# beatrix_B_v1_1.net
KiCad netlist of a schematic drawn in EAGLE
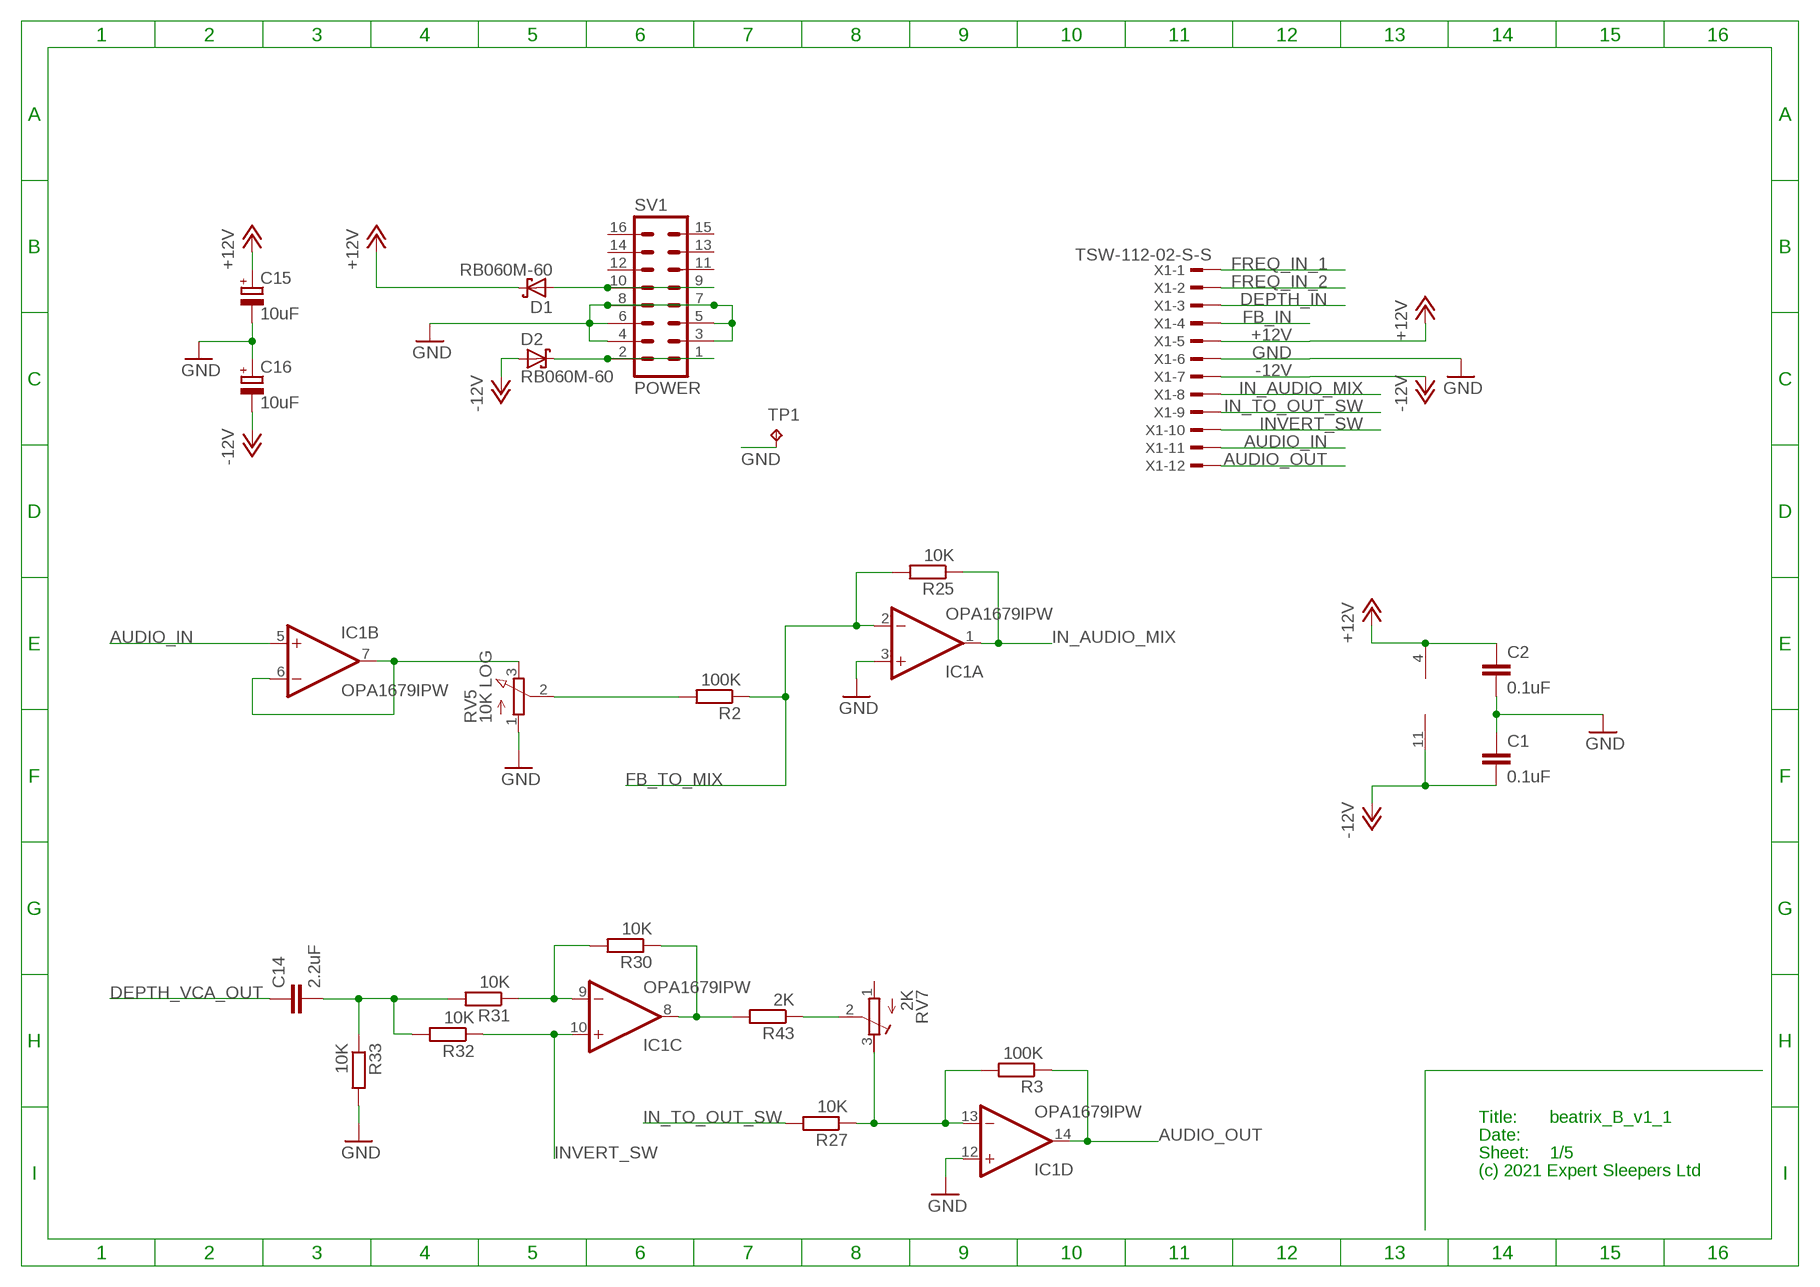
[diagram p0: schematic, sheet 1]
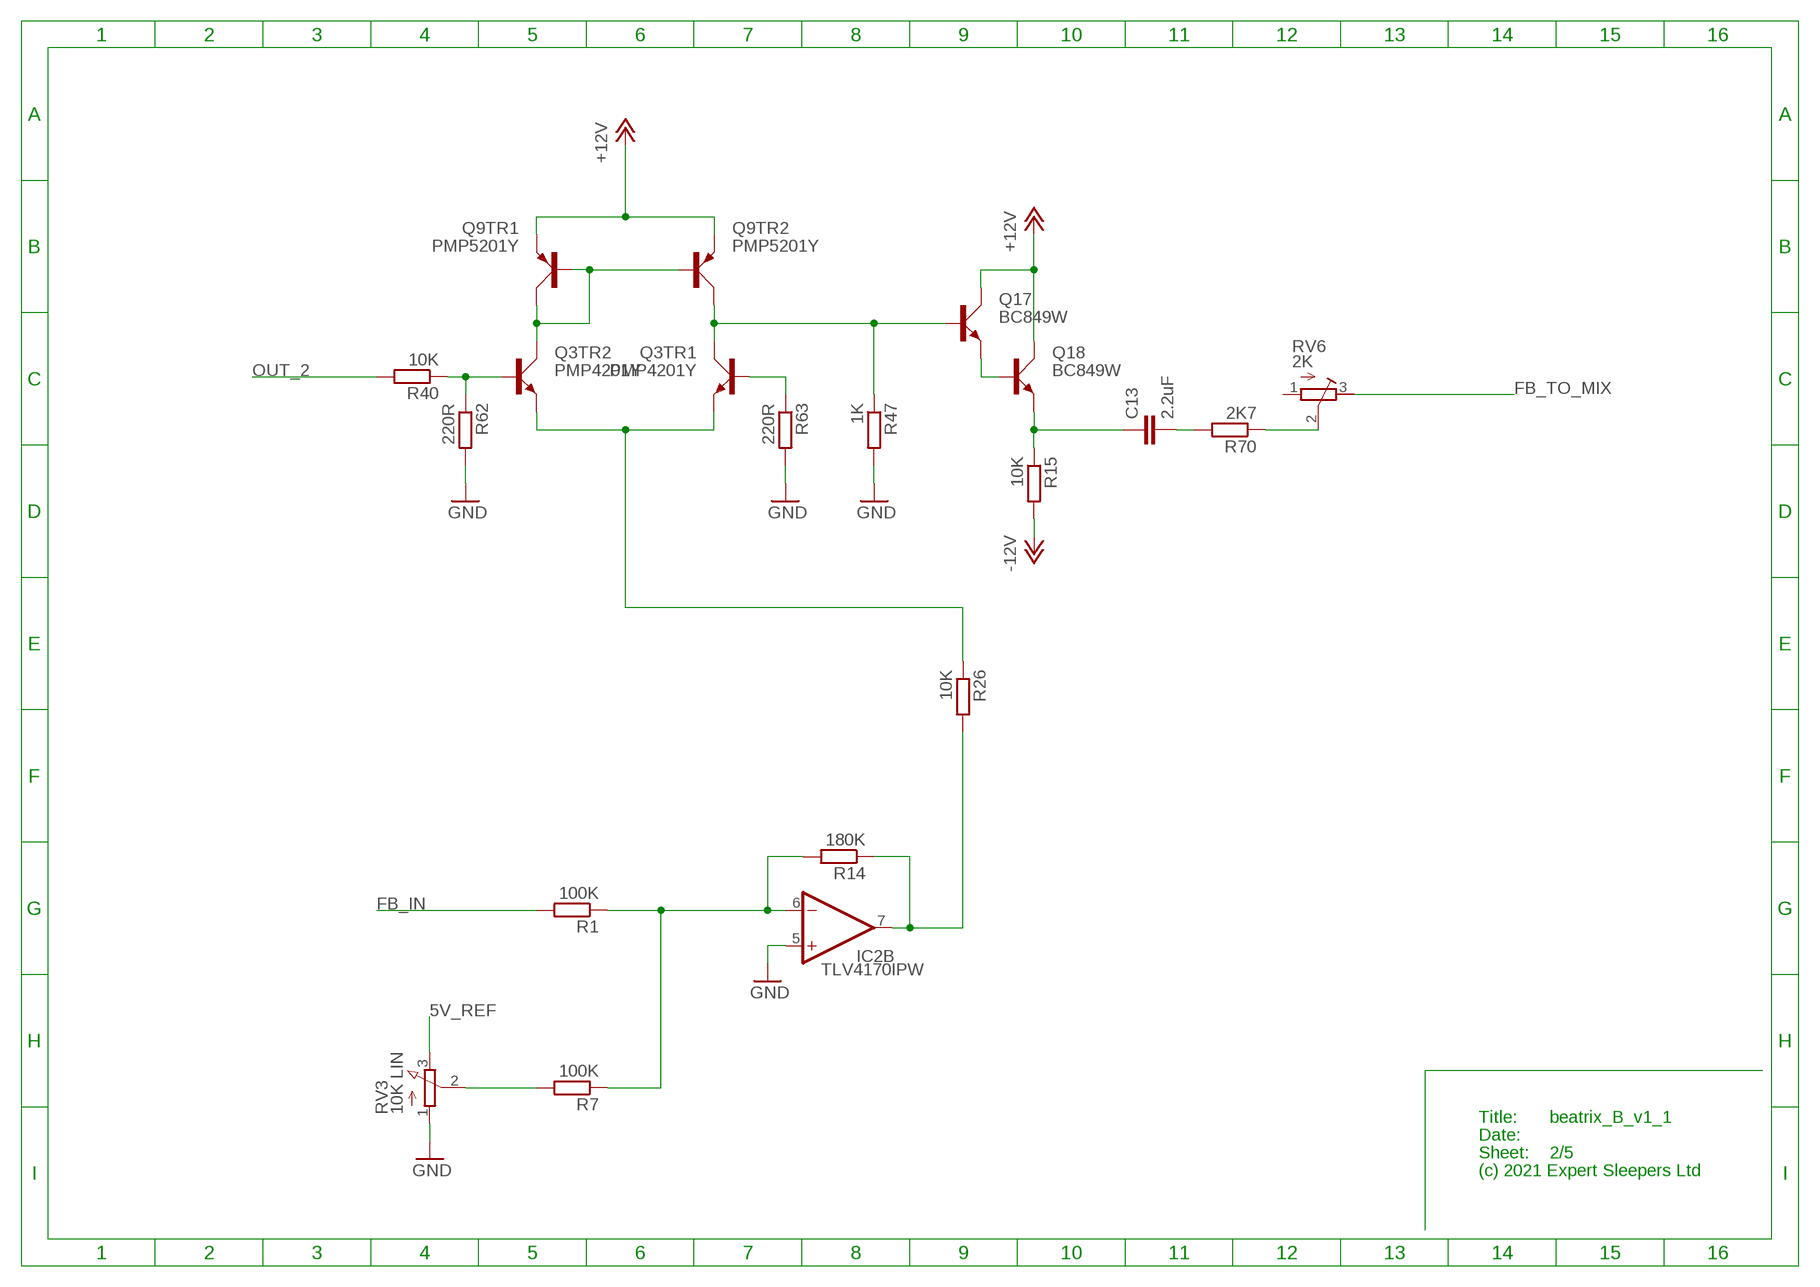
[diagram p1: schematic, sheet 2]
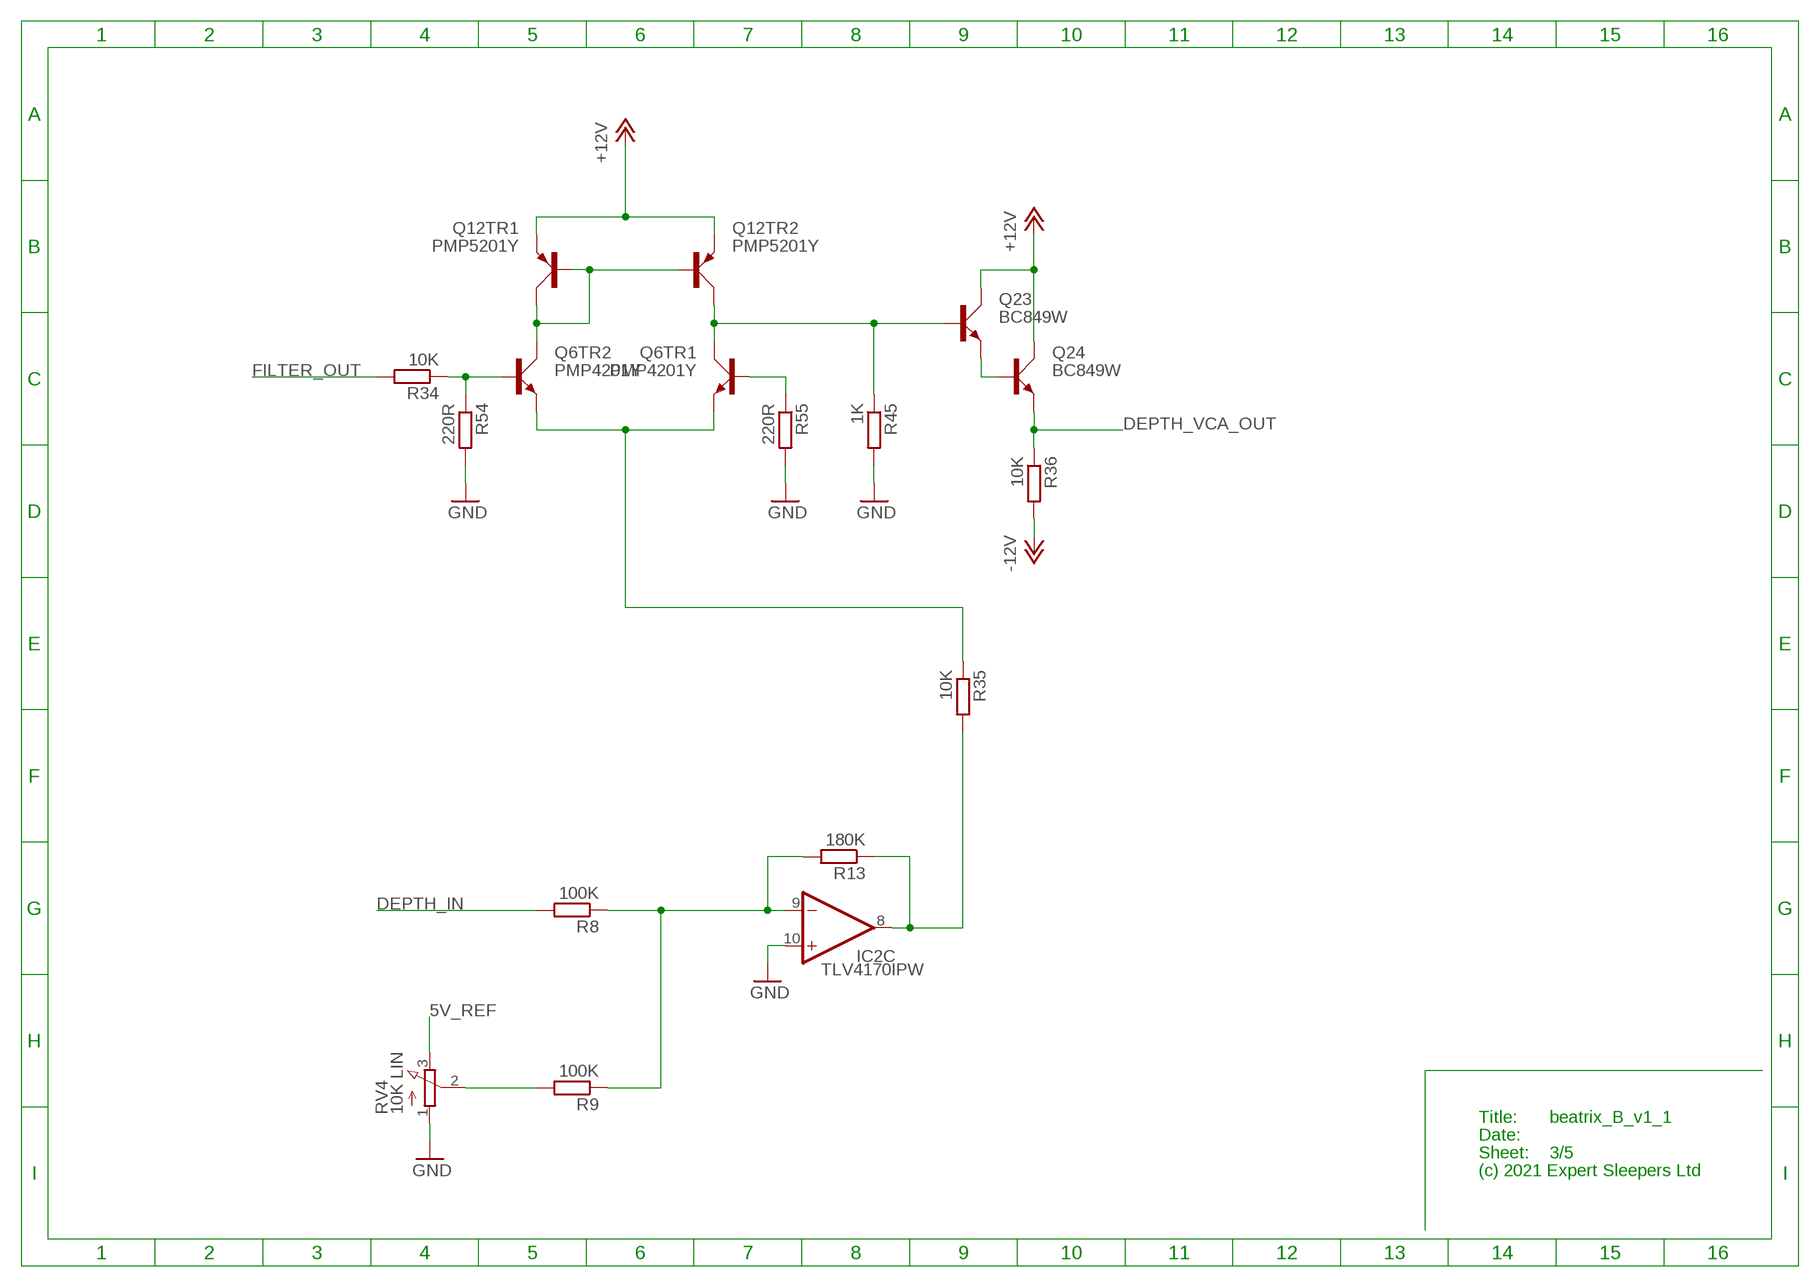
[diagram p2: schematic, sheet 3]
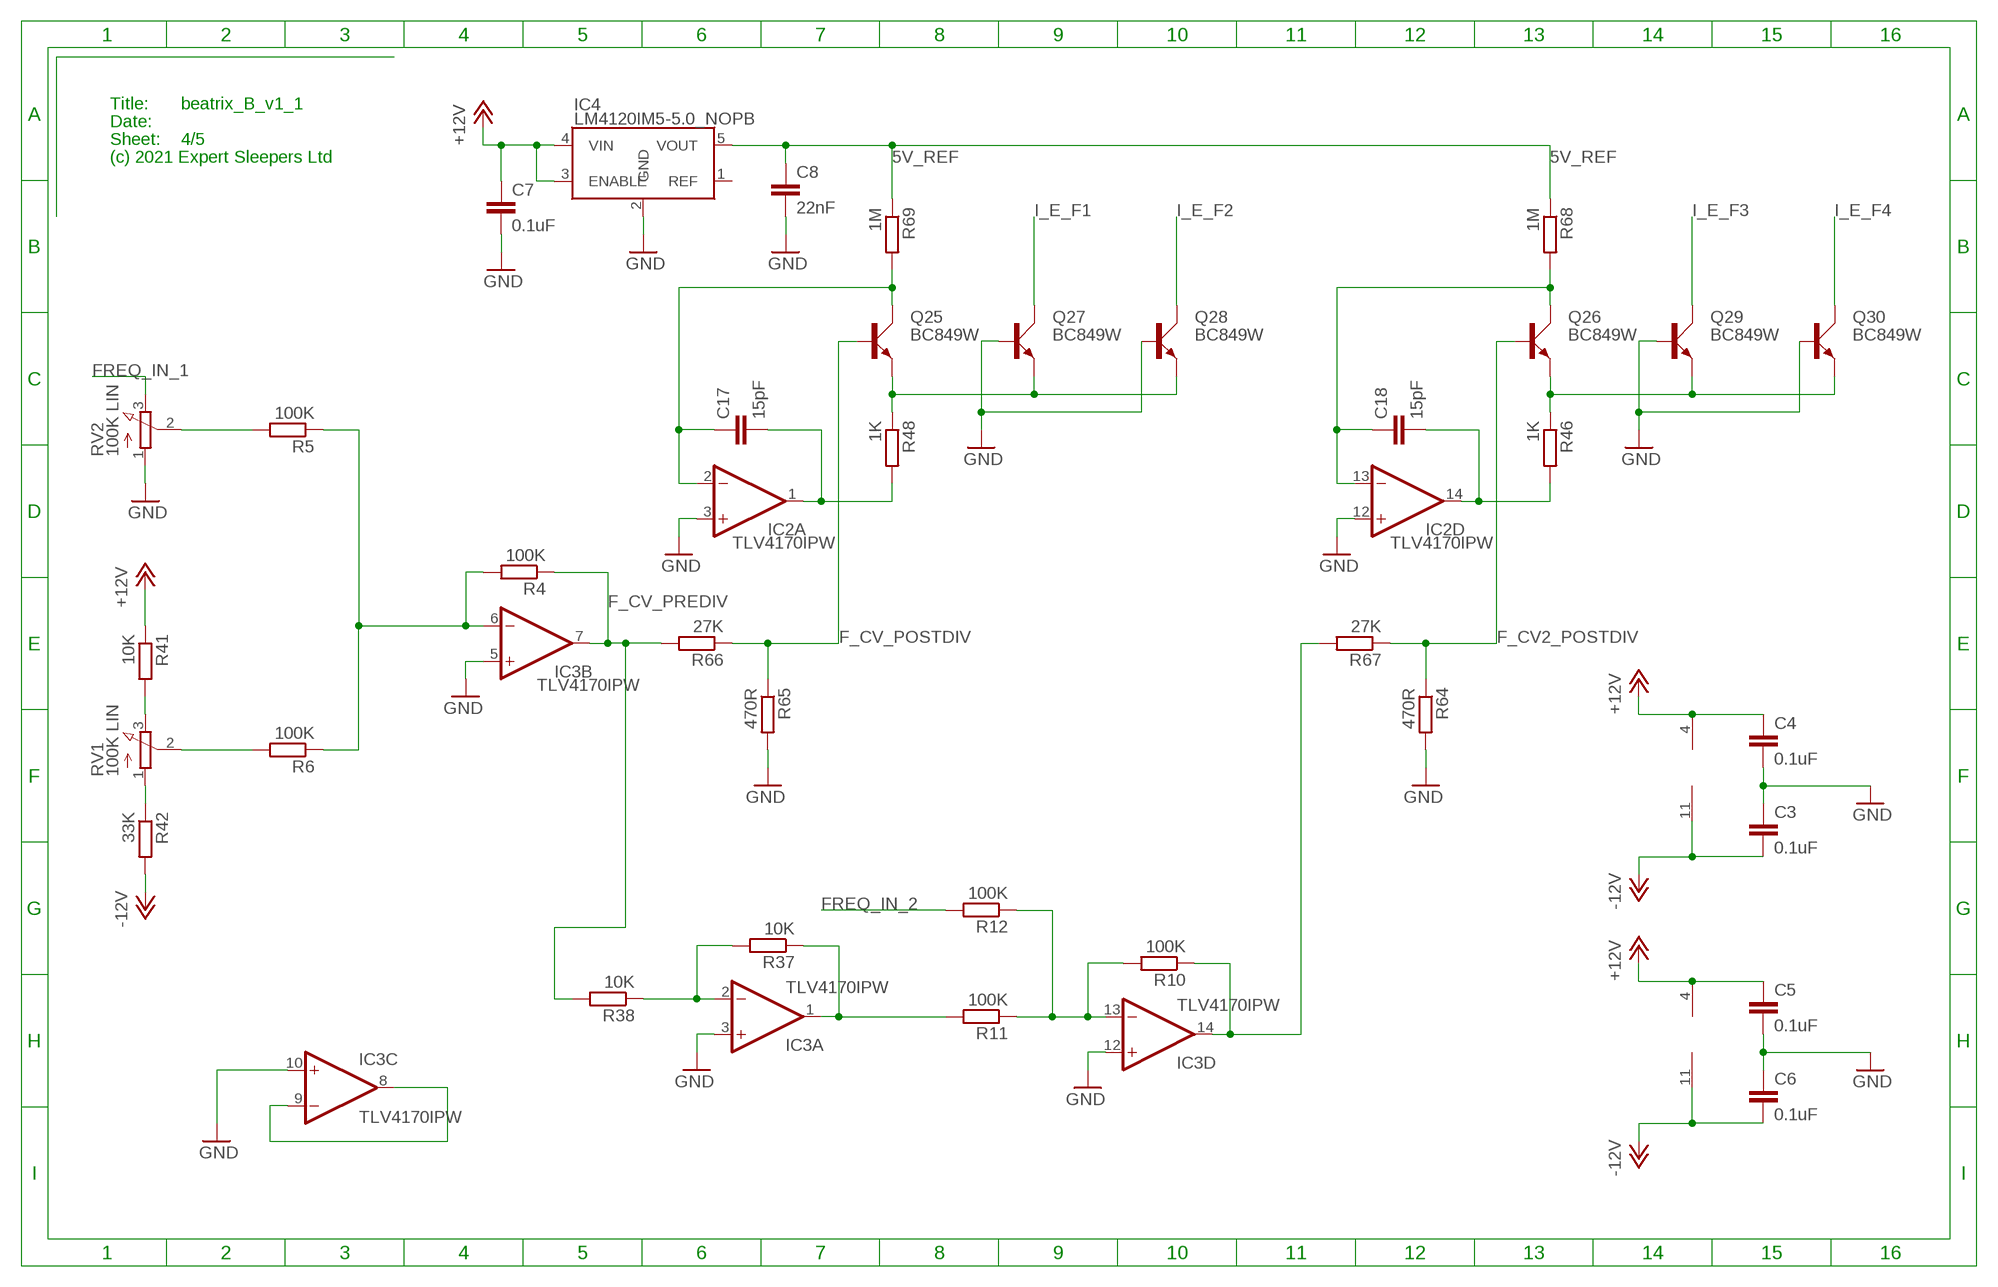
[diagram p3: schematic, sheet 4]
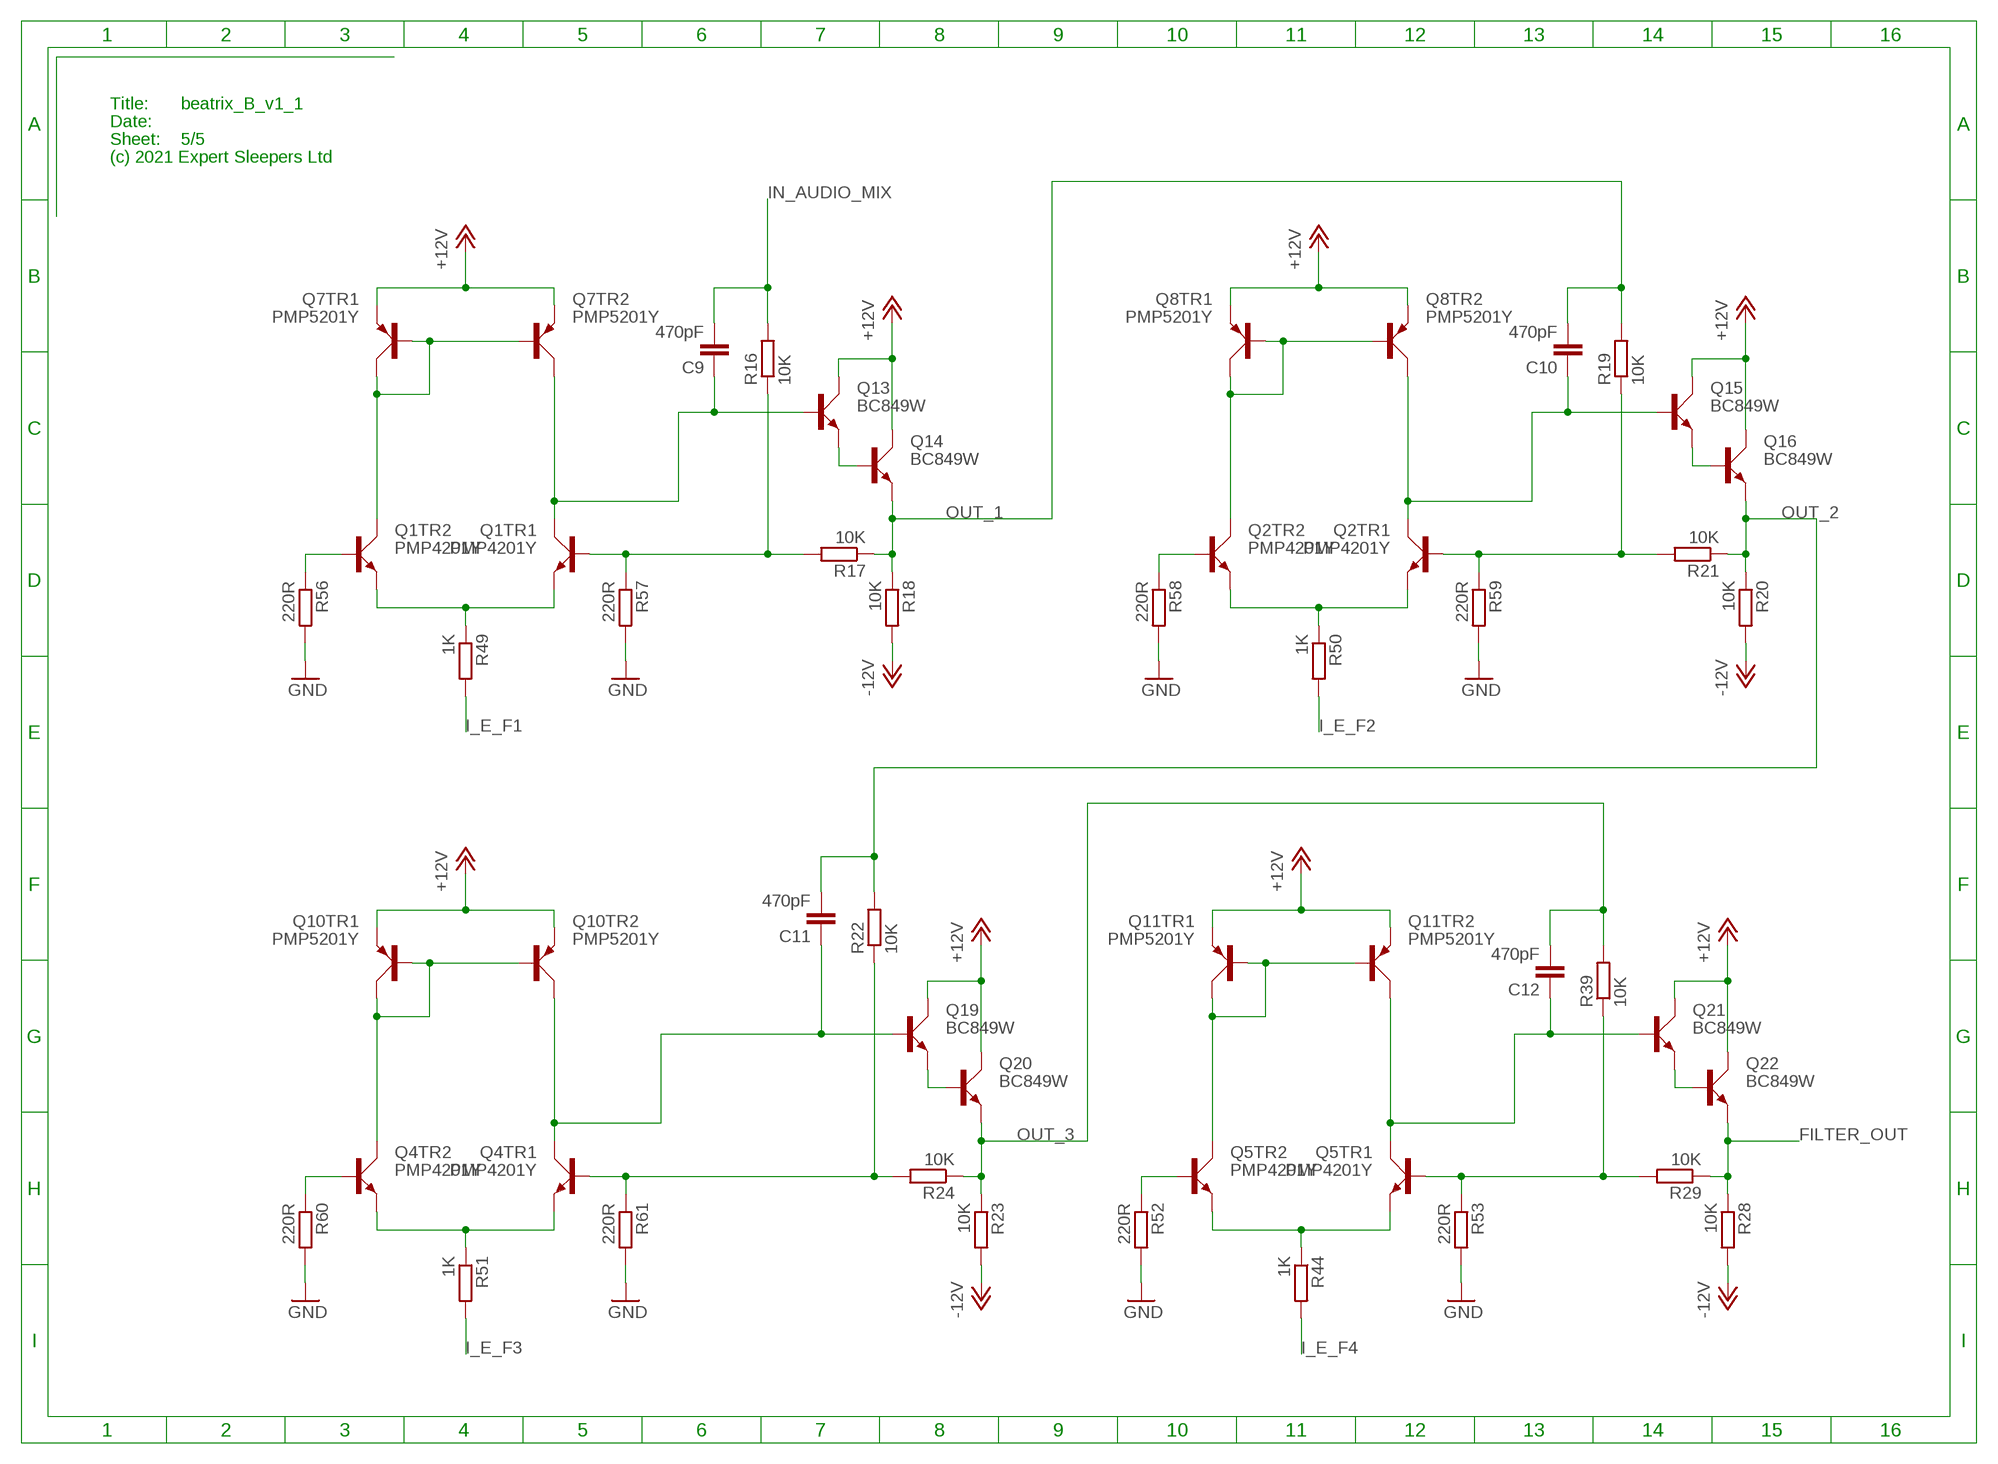
[diagram p4: schematic, sheet 5]

(export (version "E")
  (design (tool "Eeschema 10.0.6"))
  (components
    (comp (ref "C3")
      (value "0.1uF")
      (footprint "eagle-import:C0402")
      (libsource (lib "eagle-import") (part "C-EUC0402"))
    )
    (comp (ref "C4")
      (value "0.1uF")
      (footprint "eagle-import:C0402")
      (libsource (lib "eagle-import") (part "C-EUC0402"))
    )
    (comp (ref "C5")
      (value "0.1uF")
      (footprint "eagle-import:C0402")
      (libsource (lib "eagle-import") (part "C-EUC0402"))
    )
    (comp (ref "C6")
      (value "0.1uF")
      (footprint "eagle-import:C0402")
      (libsource (lib "eagle-import") (part "C-EUC0402"))
    )
    (comp (ref "C7")
      (value "0.1uF")
      (footprint "eagle-import:C0402")
      (libsource (lib "eagle-import") (part "C-EUC0402"))
    )
    (comp (ref "C8")
      (value "22nF")
      (footprint "eagle-import:C0402")
      (libsource (lib "eagle-import") (part "C-EUC0402"))
    )
    (comp (ref "C17")
      (value "15pF")
      (footprint "eagle-import:C0402")
      (libsource (lib "eagle-import") (part "C-EUC0402"))
    )
    (comp (ref "C18")
      (value "15pF")
      (footprint "eagle-import:C0402")
      (libsource (lib "eagle-import") (part "C-EUC0402"))
    )
    (comp (ref "IC2")
      (value "TLV4170IPW")
      (footprint "eagle-import:PW_R-PDSO-G14")
      (libsource (lib "eagle-import") (part "TL074PW"))
    )
    (comp (ref "IC3")
      (value "TLV4170IPW")
      (footprint "eagle-import:PW_R-PDSO-G14")
      (libsource (lib "eagle-import") (part "TL074PW"))
    )
    (comp (ref "IC4")
      (value "LM4120IM5-5.0_NOPB")
      (footprint "eagle-import:SOT95P280X145-5N")
      (fields
        (field (name "ARROW_PART_NUMBER") "LM4120IM5-5.0/NOPB")
        (field (name "MOUSER_PART_NUMBER") "926-LM4120IM550NOPB")
      )
      (libsource (lib "eagle-import") (part "LM4120IM5-5.0_NOPB"))
    )
    (comp (ref "Q25")
      (value "BC849W")
      (footprint "eagle-import:SOT323")
      (libsource (lib "eagle-import") (part "BC849W"))
    )
    (comp (ref "Q26")
      (value "BC849W")
      (footprint "eagle-import:SOT323")
      (libsource (lib "eagle-import") (part "BC849W"))
    )
    (comp (ref "Q27")
      (value "BC849W")
      (footprint "eagle-import:SOT323")
      (libsource (lib "eagle-import") (part "BC849W"))
    )
    (comp (ref "Q28")
      (value "BC849W")
      (footprint "eagle-import:SOT323")
      (libsource (lib "eagle-import") (part "BC849W"))
    )
    (comp (ref "Q29")
      (value "BC849W")
      (footprint "eagle-import:SOT323")
      (libsource (lib "eagle-import") (part "BC849W"))
    )
    (comp (ref "Q30")
      (value "BC849W")
      (footprint "eagle-import:SOT323")
      (libsource (lib "eagle-import") (part "BC849W"))
    )
    (comp (ref "R4")
      (value "100K")
      (footprint "eagle-import:R0603")
      (libsource (lib "eagle-import") (part "R-EU_R0603"))
    )
    (comp (ref "R5")
      (value "100K")
      (footprint "eagle-import:R0603")
      (libsource (lib "eagle-import") (part "R-EU_R0603"))
    )
    (comp (ref "R6")
      (value "100K")
      (footprint "eagle-import:R0603")
      (libsource (lib "eagle-import") (part "R-EU_R0603"))
    )
    (comp (ref "R10")
      (value "100K")
      (footprint "eagle-import:R0603")
      (libsource (lib "eagle-import") (part "R-EU_R0603"))
    )
    (comp (ref "R11")
      (value "100K")
      (footprint "eagle-import:R0603")
      (libsource (lib "eagle-import") (part "R-EU_R0603"))
    )
    (comp (ref "R12")
      (value "100K")
      (footprint "eagle-import:R0603")
      (libsource (lib "eagle-import") (part "R-EU_R0603"))
    )
    (comp (ref "R37")
      (value "10K")
      (footprint "eagle-import:R0603")
      (libsource (lib "eagle-import") (part "R-EU_R0603"))
    )
    (comp (ref "R38")
      (value "10K")
      (footprint "eagle-import:R0603")
      (libsource (lib "eagle-import") (part "R-EU_R0603"))
    )
    (comp (ref "R41")
      (value "10K")
      (footprint "eagle-import:R0603")
      (libsource (lib "eagle-import") (part "R-EU_R0603"))
    )
    (comp (ref "R42")
      (value "33K")
      (footprint "eagle-import:R0603")
      (libsource (lib "eagle-import") (part "R-EU_R0603"))
    )
    (comp (ref "R46")
      (value "1K")
      (footprint "eagle-import:R0603")
      (libsource (lib "eagle-import") (part "R-EU_R0603"))
    )
    (comp (ref "R48")
      (value "1K")
      (footprint "eagle-import:R0603")
      (libsource (lib "eagle-import") (part "R-EU_R0603"))
    )
    (comp (ref "R64")
      (value "470R")
      (footprint "eagle-import:R0603")
      (libsource (lib "eagle-import") (part "R-EU_R0603"))
    )
    (comp (ref "R65")
      (value "470R")
      (footprint "eagle-import:R0603")
      (libsource (lib "eagle-import") (part "R-EU_R0603"))
    )
    (comp (ref "R66")
      (value "27K")
      (footprint "eagle-import:R0603")
      (libsource (lib "eagle-import") (part "R-EU_R0603"))
    )
    (comp (ref "R67")
      (value "27K")
      (footprint "eagle-import:R0603")
      (libsource (lib "eagle-import") (part "R-EU_R0603"))
    )
    (comp (ref "R68")
      (value "1M")
      (footprint "eagle-import:R0603")
      (libsource (lib "eagle-import") (part "R-EU_R0603"))
    )
    (comp (ref "R69")
      (value "1M")
      (footprint "eagle-import:R0603")
      (libsource (lib "eagle-import") (part "R-EU_R0603"))
    )
    (comp (ref "RV1")
      (value "100K LIN")
      (footprint "eagle-import:RD1610NOA0X")
      (libsource (lib "eagle-import") (part "RD1610NOA0X"))
    )
    (comp (ref "RV2")
      (value "100K LIN")
      (footprint "eagle-import:RD1610NOA0X")
      (libsource (lib "eagle-import") (part "RD1610NOA0X"))
    )
    (comp (ref "Q6")
      (value "PMP4201Y")
      (footprint "eagle-import:SOT65P210X110-6N")
      (fields
        (field (name "ARROW_PART_NUMBER") "PMP4201Y,135")
        (field (name "MOUSER_PART_NUMBER") "771-PMP4201Y135")
      )
      (libsource (lib "eagle-import") (part "PMP4201Y"))
    )
    (comp (ref "Q12")
      (value "PMP5201Y")
      (footprint "eagle-import:SOT65P210X110-6N")
      (fields
        (field (name "ARROW_PART_NUMBER") "PMP5201Y,135")
        (field (name "MOUSER_PART_NUMBER") "771-PMP5201Y135")
      )
      (libsource (lib "eagle-import") (part "PMP5201Y"))
    )
    (comp (ref "Q23")
      (value "BC849W")
      (footprint "eagle-import:SOT323")
      (libsource (lib "eagle-import") (part "BC849W"))
    )
    (comp (ref "Q24")
      (value "BC849W")
      (footprint "eagle-import:SOT323")
      (libsource (lib "eagle-import") (part "BC849W"))
    )
    (comp (ref "R8")
      (value "100K")
      (footprint "eagle-import:R0603")
      (libsource (lib "eagle-import") (part "R-EU_R0603"))
    )
    (comp (ref "R9")
      (value "100K")
      (footprint "eagle-import:R0603")
      (libsource (lib "eagle-import") (part "R-EU_R0603"))
    )
    (comp (ref "R13")
      (value "180K")
      (footprint "eagle-import:R0603")
      (libsource (lib "eagle-import") (part "R-EU_R0603"))
    )
    (comp (ref "R34")
      (value "10K")
      (footprint "eagle-import:R0603")
      (libsource (lib "eagle-import") (part "R-EU_R0603"))
    )
    (comp (ref "R35")
      (value "10K")
      (footprint "eagle-import:R0603")
      (libsource (lib "eagle-import") (part "R-EU_R0603"))
    )
    (comp (ref "R36")
      (value "10K")
      (footprint "eagle-import:R0603")
      (libsource (lib "eagle-import") (part "R-EU_R0603"))
    )
    (comp (ref "R45")
      (value "1K")
      (footprint "eagle-import:R0603")
      (libsource (lib "eagle-import") (part "R-EU_R0603"))
    )
    (comp (ref "R54")
      (value "220R")
      (footprint "eagle-import:R0603")
      (libsource (lib "eagle-import") (part "R-EU_R0603"))
    )
    (comp (ref "R55")
      (value "220R")
      (footprint "eagle-import:R0603")
      (libsource (lib "eagle-import") (part "R-EU_R0603"))
    )
    (comp (ref "RV4")
      (value "10K LIN")
      (footprint "eagle-import:RD1610NOA0X")
      (libsource (lib "eagle-import") (part "RD1610NOA0X"))
    )
    (comp (ref "C13")
      (value "2.2uF")
      (footprint "eagle-import:C0805")
      (libsource (lib "eagle-import") (part "C-EUC0805"))
    )
    (comp (ref "Q3")
      (value "PMP4201Y")
      (footprint "eagle-import:SOT65P210X110-6N")
      (fields
        (field (name "ARROW_PART_NUMBER") "PMP4201Y,135")
        (field (name "MOUSER_PART_NUMBER") "771-PMP4201Y135")
      )
      (libsource (lib "eagle-import") (part "PMP4201Y"))
    )
    (comp (ref "Q9")
      (value "PMP5201Y")
      (footprint "eagle-import:SOT65P210X110-6N")
      (fields
        (field (name "ARROW_PART_NUMBER") "PMP5201Y,135")
        (field (name "MOUSER_PART_NUMBER") "771-PMP5201Y135")
      )
      (libsource (lib "eagle-import") (part "PMP5201Y"))
    )
    (comp (ref "Q17")
      (value "BC849W")
      (footprint "eagle-import:SOT323")
      (libsource (lib "eagle-import") (part "BC849W"))
    )
    (comp (ref "Q18")
      (value "BC849W")
      (footprint "eagle-import:SOT323")
      (libsource (lib "eagle-import") (part "BC849W"))
    )
    (comp (ref "R1")
      (value "100K")
      (footprint "eagle-import:R0603")
      (libsource (lib "eagle-import") (part "R-EU_R0603"))
    )
    (comp (ref "R7")
      (value "100K")
      (footprint "eagle-import:R0603")
      (libsource (lib "eagle-import") (part "R-EU_R0603"))
    )
    (comp (ref "R14")
      (value "180K")
      (footprint "eagle-import:R0603")
      (libsource (lib "eagle-import") (part "R-EU_R0603"))
    )
    (comp (ref "R15")
      (value "10K")
      (footprint "eagle-import:R0603")
      (libsource (lib "eagle-import") (part "R-EU_R0603"))
    )
    (comp (ref "R26")
      (value "10K")
      (footprint "eagle-import:R0603")
      (libsource (lib "eagle-import") (part "R-EU_R0603"))
    )
    (comp (ref "R40")
      (value "10K")
      (footprint "eagle-import:R0603")
      (libsource (lib "eagle-import") (part "R-EU_R0603"))
    )
    (comp (ref "R47")
      (value "1K")
      (footprint "eagle-import:R0603")
      (libsource (lib "eagle-import") (part "R-EU_R0603"))
    )
    (comp (ref "R62")
      (value "220R")
      (footprint "eagle-import:R0603")
      (libsource (lib "eagle-import") (part "R-EU_R0603"))
    )
    (comp (ref "R63")
      (value "220R")
      (footprint "eagle-import:R0603")
      (libsource (lib "eagle-import") (part "R-EU_R0603"))
    )
    (comp (ref "R70")
      (value "2K7")
      (footprint "eagle-import:R0603")
      (libsource (lib "eagle-import") (part "R-EU_R0603"))
    )
    (comp (ref "RV3")
      (value "10K LIN")
      (footprint "eagle-import:RD1610NOA0X")
      (libsource (lib "eagle-import") (part "RD1610NOA0X"))
    )
    (comp (ref "RV6")
      (value "2K")
      (footprint "eagle-import:TC33X")
      (libsource (lib "eagle-import") (part "TC33X"))
    )
    (comp (ref "C9")
      (value "470pF")
      (footprint "eagle-import:C0603")
      (libsource (lib "eagle-import") (part "C-EUC0603"))
    )
    (comp (ref "C10")
      (value "470pF")
      (footprint "eagle-import:C0603")
      (libsource (lib "eagle-import") (part "C-EUC0603"))
    )
    (comp (ref "C11")
      (value "470pF")
      (footprint "eagle-import:C0603")
      (libsource (lib "eagle-import") (part "C-EUC0603"))
    )
    (comp (ref "C12")
      (value "470pF")
      (footprint "eagle-import:C0603")
      (libsource (lib "eagle-import") (part "C-EUC0603"))
    )
    (comp (ref "Q1")
      (value "PMP4201Y")
      (footprint "eagle-import:SOT65P210X110-6N")
      (fields
        (field (name "ARROW_PART_NUMBER") "PMP4201Y,135")
        (field (name "MOUSER_PART_NUMBER") "771-PMP4201Y135")
      )
      (libsource (lib "eagle-import") (part "PMP4201Y"))
    )
    (comp (ref "Q2")
      (value "PMP4201Y")
      (footprint "eagle-import:SOT65P210X110-6N")
      (fields
        (field (name "ARROW_PART_NUMBER") "PMP4201Y,135")
        (field (name "MOUSER_PART_NUMBER") "771-PMP4201Y135")
      )
      (libsource (lib "eagle-import") (part "PMP4201Y"))
    )
    (comp (ref "Q4")
      (value "PMP4201Y")
      (footprint "eagle-import:SOT65P210X110-6N")
      (fields
        (field (name "ARROW_PART_NUMBER") "PMP4201Y,135")
        (field (name "MOUSER_PART_NUMBER") "771-PMP4201Y135")
      )
      (libsource (lib "eagle-import") (part "PMP4201Y"))
    )
    (comp (ref "Q5")
      (value "PMP4201Y")
      (footprint "eagle-import:SOT65P210X110-6N")
      (fields
        (field (name "ARROW_PART_NUMBER") "PMP4201Y,135")
        (field (name "MOUSER_PART_NUMBER") "771-PMP4201Y135")
      )
      (libsource (lib "eagle-import") (part "PMP4201Y"))
    )
    (comp (ref "Q7")
      (value "PMP5201Y")
      (footprint "eagle-import:SOT65P210X110-6N")
      (fields
        (field (name "ARROW_PART_NUMBER") "PMP5201Y,135")
        (field (name "MOUSER_PART_NUMBER") "771-PMP5201Y135")
      )
      (libsource (lib "eagle-import") (part "PMP5201Y"))
    )
    (comp (ref "Q8")
      (value "PMP5201Y")
      (footprint "eagle-import:SOT65P210X110-6N")
      (fields
        (field (name "ARROW_PART_NUMBER") "PMP5201Y,135")
        (field (name "MOUSER_PART_NUMBER") "771-PMP5201Y135")
      )
      (libsource (lib "eagle-import") (part "PMP5201Y"))
    )
    (comp (ref "Q10")
      (value "PMP5201Y")
      (footprint "eagle-import:SOT65P210X110-6N")
      (fields
        (field (name "ARROW_PART_NUMBER") "PMP5201Y,135")
        (field (name "MOUSER_PART_NUMBER") "771-PMP5201Y135")
      )
      (libsource (lib "eagle-import") (part "PMP5201Y"))
    )
    (comp (ref "Q11")
      (value "PMP5201Y")
      (footprint "eagle-import:SOT65P210X110-6N")
      (fields
        (field (name "ARROW_PART_NUMBER") "PMP5201Y,135")
        (field (name "MOUSER_PART_NUMBER") "771-PMP5201Y135")
      )
      (libsource (lib "eagle-import") (part "PMP5201Y"))
    )
    (comp (ref "Q13")
      (value "BC849W")
      (footprint "eagle-import:SOT323")
      (libsource (lib "eagle-import") (part "BC849W"))
    )
    (comp (ref "Q14")
      (value "BC849W")
      (footprint "eagle-import:SOT323")
      (libsource (lib "eagle-import") (part "BC849W"))
    )
    (comp (ref "Q15")
      (value "BC849W")
      (footprint "eagle-import:SOT323")
      (libsource (lib "eagle-import") (part "BC849W"))
    )
    (comp (ref "Q16")
      (value "BC849W")
      (footprint "eagle-import:SOT323")
      (libsource (lib "eagle-import") (part "BC849W"))
    )
    (comp (ref "Q19")
      (value "BC849W")
      (footprint "eagle-import:SOT323")
      (libsource (lib "eagle-import") (part "BC849W"))
    )
    (comp (ref "Q20")
      (value "BC849W")
      (footprint "eagle-import:SOT323")
      (libsource (lib "eagle-import") (part "BC849W"))
    )
    (comp (ref "Q21")
      (value "BC849W")
      (footprint "eagle-import:SOT323")
      (libsource (lib "eagle-import") (part "BC849W"))
    )
    (comp (ref "Q22")
      (value "BC849W")
      (footprint "eagle-import:SOT323")
      (libsource (lib "eagle-import") (part "BC849W"))
    )
    (comp (ref "R16")
      (value "10K")
      (footprint "eagle-import:R0603")
      (libsource (lib "eagle-import") (part "R-EU_R0603"))
    )
    (comp (ref "R17")
      (value "10K")
      (footprint "eagle-import:R0603")
      (libsource (lib "eagle-import") (part "R-EU_R0603"))
    )
    (comp (ref "R18")
      (value "10K")
      (footprint "eagle-import:R0603")
      (libsource (lib "eagle-import") (part "R-EU_R0603"))
    )
    (comp (ref "R19")
      (value "10K")
      (footprint "eagle-import:R0603")
      (libsource (lib "eagle-import") (part "R-EU_R0603"))
    )
    (comp (ref "R20")
      (value "10K")
      (footprint "eagle-import:R0603")
      (libsource (lib "eagle-import") (part "R-EU_R0603"))
    )
    (comp (ref "R21")
      (value "10K")
      (footprint "eagle-import:R0603")
      (libsource (lib "eagle-import") (part "R-EU_R0603"))
    )
    (comp (ref "R22")
      (value "10K")
      (footprint "eagle-import:R0603")
      (libsource (lib "eagle-import") (part "R-EU_R0603"))
    )
    (comp (ref "R23")
      (value "10K")
      (footprint "eagle-import:R0603")
      (libsource (lib "eagle-import") (part "R-EU_R0603"))
    )
    (comp (ref "R24")
      (value "10K")
      (footprint "eagle-import:R0603")
      (libsource (lib "eagle-import") (part "R-EU_R0603"))
    )
    (comp (ref "R28")
      (value "10K")
      (footprint "eagle-import:R0603")
      (libsource (lib "eagle-import") (part "R-EU_R0603"))
    )
    (comp (ref "R29")
      (value "10K")
      (footprint "eagle-import:R0603")
      (libsource (lib "eagle-import") (part "R-EU_R0603"))
    )
    (comp (ref "R39")
      (value "10K")
      (footprint "eagle-import:R0603")
      (libsource (lib "eagle-import") (part "R-EU_R0603"))
    )
    (comp (ref "R44")
      (value "1K")
      (footprint "eagle-import:R0603")
      (libsource (lib "eagle-import") (part "R-EU_R0603"))
    )
    (comp (ref "R49")
      (value "1K")
      (footprint "eagle-import:R0603")
      (libsource (lib "eagle-import") (part "R-EU_R0603"))
    )
    (comp (ref "R50")
      (value "1K")
      (footprint "eagle-import:R0603")
      (libsource (lib "eagle-import") (part "R-EU_R0603"))
    )
    (comp (ref "R51")
      (value "1K")
      (footprint "eagle-import:R0603")
      (libsource (lib "eagle-import") (part "R-EU_R0603"))
    )
    (comp (ref "R52")
      (value "220R")
      (footprint "eagle-import:R0603")
      (libsource (lib "eagle-import") (part "R-EU_R0603"))
    )
    (comp (ref "R53")
      (value "220R")
      (footprint "eagle-import:R0603")
      (libsource (lib "eagle-import") (part "R-EU_R0603"))
    )
    (comp (ref "R56")
      (value "220R")
      (footprint "eagle-import:R0603")
      (libsource (lib "eagle-import") (part "R-EU_R0603"))
    )
    (comp (ref "R57")
      (value "220R")
      (footprint "eagle-import:R0603")
      (libsource (lib "eagle-import") (part "R-EU_R0603"))
    )
    (comp (ref "R58")
      (value "220R")
      (footprint "eagle-import:R0603")
      (libsource (lib "eagle-import") (part "R-EU_R0603"))
    )
    (comp (ref "R59")
      (value "220R")
      (footprint "eagle-import:R0603")
      (libsource (lib "eagle-import") (part "R-EU_R0603"))
    )
    (comp (ref "R60")
      (value "220R")
      (footprint "eagle-import:R0603")
      (libsource (lib "eagle-import") (part "R-EU_R0603"))
    )
    (comp (ref "R61")
      (value "220R")
      (footprint "eagle-import:R0603")
      (libsource (lib "eagle-import") (part "R-EU_R0603"))
    )
    (comp (ref "C1")
      (value "0.1uF")
      (footprint "eagle-import:C0402")
      (libsource (lib "eagle-import") (part "C-EUC0402"))
    )
    (comp (ref "C2")
      (value "0.1uF")
      (footprint "eagle-import:C0402")
      (libsource (lib "eagle-import") (part "C-EUC0402"))
    )
    (comp (ref "C14")
      (value "2.2uF")
      (footprint "eagle-import:C0805")
      (libsource (lib "eagle-import") (part "C-EUC0805"))
    )
    (comp (ref "C15")
      (value "10uF")
      (footprint "eagle-import:UD-4X5,8_NICHICON")
      (libsource (lib "eagle-import") (part "CPOL-EUUD-4X5,8"))
    )
    (comp (ref "C16")
      (value "10uF")
      (footprint "eagle-import:UD-4X5,8_NICHICON")
      (libsource (lib "eagle-import") (part "CPOL-EUUD-4X5,8"))
    )
    (comp (ref "D1")
      (value "RB060M-60")
      (footprint "eagle-import:SOD123FL")
      (libsource (lib "eagle-import") (part "RB060M-60"))
    )
    (comp (ref "D2")
      (value "RB060M-60")
      (footprint "eagle-import:SOD123FL")
      (libsource (lib "eagle-import") (part "RB060M-60"))
    )
    (comp (ref "IC1")
      (value "OPA1679IPW")
      (footprint "eagle-import:PW_R-PDSO-G14")
      (libsource (lib "eagle-import") (part "TL074PW"))
    )
    (comp (ref "R2")
      (value "100K")
      (footprint "eagle-import:R0603")
      (libsource (lib "eagle-import") (part "R-EU_R0603"))
    )
    (comp (ref "R3")
      (value "100K")
      (footprint "eagle-import:R0603")
      (libsource (lib "eagle-import") (part "R-EU_R0603"))
    )
    (comp (ref "R25")
      (value "10K")
      (footprint "eagle-import:R0603")
      (libsource (lib "eagle-import") (part "R-EU_R0603"))
    )
    (comp (ref "R27")
      (value "10K")
      (footprint "eagle-import:R0603")
      (libsource (lib "eagle-import") (part "R-EU_R0603"))
    )
    (comp (ref "R30")
      (value "10K")
      (footprint "eagle-import:R0603")
      (libsource (lib "eagle-import") (part "R-EU_R0603"))
    )
    (comp (ref "R31")
      (value "10K")
      (footprint "eagle-import:R0603")
      (libsource (lib "eagle-import") (part "R-EU_R0603"))
    )
    (comp (ref "R32")
      (value "10K")
      (footprint "eagle-import:R0603")
      (libsource (lib "eagle-import") (part "R-EU_R0603"))
    )
    (comp (ref "R33")
      (value "10K")
      (footprint "eagle-import:R0603")
      (libsource (lib "eagle-import") (part "R-EU_R0603"))
    )
    (comp (ref "R43")
      (value "2K")
      (footprint "eagle-import:R0603")
      (libsource (lib "eagle-import") (part "R-EU_R0603"))
    )
    (comp (ref "RV5")
      (value "10K LOG")
      (footprint "eagle-import:RD1610NOA0X")
      (libsource (lib "eagle-import") (part "RD1610NOA0X"))
    )
    (comp (ref "RV7")
      (value "2K")
      (footprint "eagle-import:TC33X")
      (libsource (lib "eagle-import") (part "TC33X"))
    )
    (comp (ref "SV1")
      (value "POWER")
      (footprint "eagle-import:ML16")
      (libsource (lib "eagle-import") (part "ML16"))
    )
    (comp (ref "TP1")
      (value "RA2")
      (footprint "eagle-import:P1-13")
      (libsource (lib "eagle-import") (part "TPPAD1-13"))
    )
    (comp (ref "X1")
      (value "TSW-112-02-S-S")
      (footprint "eagle-import:TSW-112-02-S-S")
      (libsource (lib "eagle-import") (part "TSW-112-02-S-S"))
    )
  )
  (nets
    (net (code "1") (name "+12V") (class "Default")
      (node (ref "C15") (pin "+") (pinfunction "+_+") (pintype "passive"))
      (node (ref "C2") (pin "1") (pinfunction "1_1") (pintype "passive"))
      (node (ref "C4") (pin "1") (pinfunction "1_1") (pintype "passive"))
      (node (ref "C5") (pin "1") (pinfunction "1_1") (pintype "passive"))
      (node (ref "C7") (pin "1") (pinfunction "1_1") (pintype "passive"))
      (node (ref "D1") (pin "C") (pinfunction "C_C") (pintype "passive"))
      (node (ref "IC1") (pin "4") (pinfunction "V+_4") (pintype "power_in"))
      (node (ref "IC2") (pin "4") (pinfunction "V+_4") (pintype "power_in"))
      (node (ref "IC3") (pin "4") (pinfunction "V+_4") (pintype "power_in"))
      (node (ref "IC4") (pin "3") (pinfunction "ENABLE_3") (pintype "input"))
      (node (ref "IC4") (pin "4") (pinfunction "VIN_4") (pintype "power_in"))
      (node (ref "Q10") (pin "4") (pinfunction "E_4") (pintype "passive"))
      (node (ref "Q10") (pin "5") (pinfunction "E_5") (pintype "passive"))
      (node (ref "Q11") (pin "4") (pinfunction "E_4") (pintype "passive"))
      (node (ref "Q11") (pin "5") (pinfunction "E_5") (pintype "passive"))
      (node (ref "Q12") (pin "4") (pinfunction "E_4") (pintype "passive"))
      (node (ref "Q12") (pin "5") (pinfunction "E_5") (pintype "passive"))
      (node (ref "Q13") (pin "3") (pinfunction "C_3") (pintype "passive"))
      (node (ref "Q14") (pin "3") (pinfunction "C_3") (pintype "passive"))
      (node (ref "Q15") (pin "3") (pinfunction "C_3") (pintype "passive"))
      (node (ref "Q16") (pin "3") (pinfunction "C_3") (pintype "passive"))
      (node (ref "Q17") (pin "3") (pinfunction "C_3") (pintype "passive"))
      (node (ref "Q18") (pin "3") (pinfunction "C_3") (pintype "passive"))
      (node (ref "Q19") (pin "3") (pinfunction "C_3") (pintype "passive"))
      (node (ref "Q20") (pin "3") (pinfunction "C_3") (pintype "passive"))
      (node (ref "Q21") (pin "3") (pinfunction "C_3") (pintype "passive"))
      (node (ref "Q22") (pin "3") (pinfunction "C_3") (pintype "passive"))
      (node (ref "Q23") (pin "3") (pinfunction "C_3") (pintype "passive"))
      (node (ref "Q24") (pin "3") (pinfunction "C_3") (pintype "passive"))
      (node (ref "Q7") (pin "4") (pinfunction "E_4") (pintype "passive"))
      (node (ref "Q7") (pin "5") (pinfunction "E_5") (pintype "passive"))
      (node (ref "Q8") (pin "4") (pinfunction "E_4") (pintype "passive"))
      (node (ref "Q8") (pin "5") (pinfunction "E_5") (pintype "passive"))
      (node (ref "Q9") (pin "4") (pinfunction "E_4") (pintype "passive"))
      (node (ref "Q9") (pin "5") (pinfunction "E_5") (pintype "passive"))
      (node (ref "R41") (pin "1") (pinfunction "1_1") (pintype "passive"))
      (node (ref "X1") (pin "5") (pinfunction "1_5") (pintype "passive"))
    )
    (net (code "2") (name "-12V") (class "Default")
      (node (ref "C1") (pin "2") (pinfunction "2_2") (pintype "passive"))
      (node (ref "C16") (pin "-") (pinfunction "-_-") (pintype "passive"))
      (node (ref "C3") (pin "2") (pinfunction "2_2") (pintype "passive"))
      (node (ref "C6") (pin "2") (pinfunction "2_2") (pintype "passive"))
      (node (ref "D2") (pin "A") (pinfunction "A_A") (pintype "passive"))
      (node (ref "IC1") (pin "11") (pinfunction "V-_11") (pintype "power_in"))
      (node (ref "IC2") (pin "11") (pinfunction "V-_11") (pintype "power_in"))
      (node (ref "IC3") (pin "11") (pinfunction "V-_11") (pintype "power_in"))
      (node (ref "R15") (pin "2") (pinfunction "2_2") (pintype "passive"))
      (node (ref "R18") (pin "2") (pinfunction "2_2") (pintype "passive"))
      (node (ref "R20") (pin "2") (pinfunction "2_2") (pintype "passive"))
      (node (ref "R23") (pin "2") (pinfunction "2_2") (pintype "passive"))
      (node (ref "R28") (pin "2") (pinfunction "2_2") (pintype "passive"))
      (node (ref "R36") (pin "2") (pinfunction "2_2") (pintype "passive"))
      (node (ref "R42") (pin "2") (pinfunction "2_2") (pintype "passive"))
      (node (ref "X1") (pin "7") (pinfunction "1_7") (pintype "passive"))
    )
    (net (code "3") (name "5V_REF") (class "Default")
      (node (ref "C8") (pin "1") (pinfunction "1_1") (pintype "passive"))
      (node (ref "IC4") (pin "5") (pinfunction "VOUT_5") (pintype "output"))
      (node (ref "R68") (pin "1") (pinfunction "1_1") (pintype "passive"))
      (node (ref "R69") (pin "1") (pinfunction "1_1") (pintype "passive"))
      (node (ref "RV3") (pin "3") (pinfunction "E_3") (pintype "passive"))
      (node (ref "RV4") (pin "3") (pinfunction "E_3") (pintype "passive"))
    )
    (net (code "4") (name "AUDIO_IN") (class "Default")
      (node (ref "IC1") (pin "5") (pinfunction "+IN_5") (pintype "input"))
      (node (ref "X1") (pin "11") (pinfunction "1_11") (pintype "passive"))
    )
    (net (code "5") (name "AUDIO_OUT") (class "Default")
      (node (ref "IC1") (pin "14") (pinfunction "OUT_14") (pintype "output"))
      (node (ref "R3") (pin "1") (pinfunction "1_1") (pintype "passive"))
      (node (ref "X1") (pin "12") (pinfunction "1_12") (pintype "passive"))
    )
    (net (code "6") (name "DEPTH_IN") (class "Default")
      (node (ref "R8") (pin "2") (pinfunction "2_2") (pintype "passive"))
      (node (ref "X1") (pin "3") (pinfunction "1_3") (pintype "passive"))
    )
    (net (code "7") (name "DEPTH_VCA_OUT") (class "Default")
      (node (ref "C14") (pin "1") (pinfunction "1_1") (pintype "passive"))
      (node (ref "Q24") (pin "2") (pinfunction "E_2") (pintype "passive"))
      (node (ref "R36") (pin "1") (pinfunction "1_1") (pintype "passive"))
    )
    (net (code "8") (name "FB_IN") (class "Default")
      (node (ref "R1") (pin "2") (pinfunction "2_2") (pintype "passive"))
      (node (ref "X1") (pin "4") (pinfunction "1_4") (pintype "passive"))
    )
    (net (code "9") (name "FB_TO_MIX") (class "Default")
      (node (ref "IC1") (pin "2") (pinfunction "-IN_2") (pintype "input"))
      (node (ref "R2") (pin "1") (pinfunction "1_1") (pintype "passive"))
      (node (ref "R25") (pin "2") (pinfunction "2_2") (pintype "passive"))
      (node (ref "RV6") (pin "3") (pinfunction "E_3") (pintype "passive"))
    )
    (net (code "10") (name "FILTER_OUT") (class "Default")
      (node (ref "Q22") (pin "2") (pinfunction "E_2") (pintype "passive"))
      (node (ref "R28") (pin "1") (pinfunction "1_1") (pintype "passive"))
      (node (ref "R29") (pin "1") (pinfunction "1_1") (pintype "passive"))
      (node (ref "R34") (pin "2") (pinfunction "2_2") (pintype "passive"))
    )
    (net (code "11") (name "FREQ_IN_1") (class "Default")
      (node (ref "RV2") (pin "3") (pinfunction "E_3") (pintype "passive"))
      (node (ref "X1") (pin "1") (pinfunction "1_1") (pintype "passive"))
    )
    (net (code "12") (name "FREQ_IN_2") (class "Default")
      (node (ref "R12") (pin "2") (pinfunction "2_2") (pintype "passive"))
      (node (ref "X1") (pin "2") (pinfunction "1_2") (pintype "passive"))
    )
    (net (code "13") (name "F_CV2_POSTDIV") (class "Default")
      (node (ref "Q26") (pin "1") (pinfunction "B_1") (pintype "passive"))
      (node (ref "R64") (pin "1") (pinfunction "1_1") (pintype "passive"))
      (node (ref "R67") (pin "1") (pinfunction "1_1") (pintype "passive"))
    )
    (net (code "14") (name "F_CV_POSTDIV") (class "Default")
      (node (ref "Q25") (pin "1") (pinfunction "B_1") (pintype "passive"))
      (node (ref "R65") (pin "1") (pinfunction "1_1") (pintype "passive"))
      (node (ref "R66") (pin "1") (pinfunction "1_1") (pintype "passive"))
    )
    (net (code "15") (name "F_CV_PREDIV") (class "Default")
      (node (ref "IC3") (pin "7") (pinfunction "OUT_7") (pintype "output"))
      (node (ref "R38") (pin "2") (pinfunction "2_2") (pintype "passive"))
      (node (ref "R4") (pin "1") (pinfunction "1_1") (pintype "passive"))
      (node (ref "R66") (pin "2") (pinfunction "2_2") (pintype "passive"))
    )
    (net (code "16") (name "GND") (class "Default")
      (node (ref "C1") (pin "1") (pinfunction "1_1") (pintype "passive"))
      (node (ref "C15") (pin "-") (pinfunction "-_-") (pintype "passive"))
      (node (ref "C16") (pin "+") (pinfunction "+_+") (pintype "passive"))
      (node (ref "C2") (pin "2") (pinfunction "2_2") (pintype "passive"))
      (node (ref "C3") (pin "1") (pinfunction "1_1") (pintype "passive"))
      (node (ref "C4") (pin "2") (pinfunction "2_2") (pintype "passive"))
      (node (ref "C5") (pin "2") (pinfunction "2_2") (pintype "passive"))
      (node (ref "C6") (pin "1") (pinfunction "1_1") (pintype "passive"))
      (node (ref "C7") (pin "2") (pinfunction "2_2") (pintype "passive"))
      (node (ref "C8") (pin "2") (pinfunction "2_2") (pintype "passive"))
      (node (ref "IC1") (pin "12") (pinfunction "+IN_12") (pintype "input"))
      (node (ref "IC1") (pin "3") (pinfunction "+IN_3") (pintype "input"))
      (node (ref "IC2") (pin "10") (pinfunction "+IN_10") (pintype "input"))
      (node (ref "IC2") (pin "12") (pinfunction "+IN_12") (pintype "input"))
      (node (ref "IC2") (pin "3") (pinfunction "+IN_3") (pintype "input"))
      (node (ref "IC2") (pin "5") (pinfunction "+IN_5") (pintype "input"))
      (node (ref "IC3") (pin "10") (pinfunction "+IN_10") (pintype "input"))
      (node (ref "IC3") (pin "12") (pinfunction "+IN_12") (pintype "input"))
      (node (ref "IC3") (pin "3") (pinfunction "+IN_3") (pintype "input"))
      (node (ref "IC3") (pin "5") (pinfunction "+IN_5") (pintype "input"))
      (node (ref "IC4") (pin "2") (pinfunction "GND_2") (pintype "power_in"))
      (node (ref "Q27") (pin "1") (pinfunction "B_1") (pintype "passive"))
      (node (ref "Q28") (pin "1") (pinfunction "B_1") (pintype "passive"))
      (node (ref "Q29") (pin "1") (pinfunction "B_1") (pintype "passive"))
      (node (ref "Q30") (pin "1") (pinfunction "B_1") (pintype "passive"))
      (node (ref "R33") (pin "2") (pinfunction "2_2") (pintype "passive"))
      (node (ref "R45") (pin "2") (pinfunction "2_2") (pintype "passive"))
      (node (ref "R47") (pin "2") (pinfunction "2_2") (pintype "passive"))
      (node (ref "R52") (pin "2") (pinfunction "2_2") (pintype "passive"))
      (node (ref "R53") (pin "2") (pinfunction "2_2") (pintype "passive"))
      (node (ref "R54") (pin "2") (pinfunction "2_2") (pintype "passive"))
      (node (ref "R55") (pin "2") (pinfunction "2_2") (pintype "passive"))
      (node (ref "R56") (pin "2") (pinfunction "2_2") (pintype "passive"))
      (node (ref "R57") (pin "2") (pinfunction "2_2") (pintype "passive"))
      (node (ref "R58") (pin "2") (pinfunction "2_2") (pintype "passive"))
      (node (ref "R59") (pin "2") (pinfunction "2_2") (pintype "passive"))
      (node (ref "R60") (pin "2") (pinfunction "2_2") (pintype "passive"))
      (node (ref "R61") (pin "2") (pinfunction "2_2") (pintype "passive"))
      (node (ref "R62") (pin "2") (pinfunction "2_2") (pintype "passive"))
      (node (ref "R63") (pin "2") (pinfunction "2_2") (pintype "passive"))
      (node (ref "R64") (pin "2") (pinfunction "2_2") (pintype "passive"))
      (node (ref "R65") (pin "2") (pinfunction "2_2") (pintype "passive"))
      (node (ref "RV2") (pin "1") (pinfunction "A_1") (pintype "passive"))
      (node (ref "RV3") (pin "1") (pinfunction "A_1") (pintype "passive"))
      (node (ref "RV4") (pin "1") (pinfunction "A_1") (pintype "passive"))
      (node (ref "RV5") (pin "1") (pinfunction "A_1") (pintype "passive"))
      (node (ref "SV1") (pin "3") (pinfunction "3_3") (pintype "passive"))
      (node (ref "SV1") (pin "4") (pinfunction "4_4") (pintype "passive"))
      (node (ref "SV1") (pin "5") (pinfunction "5_5") (pintype "passive"))
      (node (ref "SV1") (pin "6") (pinfunction "6_6") (pintype "passive"))
      (node (ref "SV1") (pin "7") (pinfunction "7_7") (pintype "passive"))
      (node (ref "SV1") (pin "8") (pinfunction "8_8") (pintype "passive"))
      (node (ref "TP1") (pin "TP") (pinfunction "TP_TP") (pintype "input"))
      (node (ref "X1") (pin "6") (pinfunction "1_6") (pintype "passive"))
    )
    (net (code "17") (name "INVERT_SW") (class "Default")
      (node (ref "IC1") (pin "10") (pinfunction "+IN_10") (pintype "input"))
      (node (ref "R32") (pin "1") (pinfunction "1_1") (pintype "passive"))
      (node (ref "X1") (pin "10") (pinfunction "1_10") (pintype "passive"))
    )
    (net (code "18") (name "IN_AUDIO_MIX") (class "Default")
      (node (ref "C9") (pin "2") (pinfunction "2_2") (pintype "passive"))
      (node (ref "IC1") (pin "1") (pinfunction "OUT_1") (pintype "output"))
      (node (ref "R16") (pin "2") (pinfunction "2_2") (pintype "passive"))
      (node (ref "R25") (pin "1") (pinfunction "1_1") (pintype "passive"))
      (node (ref "X1") (pin "8") (pinfunction "1_8") (pintype "passive"))
    )
    (net (code "19") (name "IN_TO_OUT_SW") (class "Default")
      (node (ref "R27") (pin "2") (pinfunction "2_2") (pintype "passive"))
      (node (ref "X1") (pin "9") (pinfunction "1_9") (pintype "passive"))
    )
    (net (code "20") (name "I_E_F1") (class "Default")
      (node (ref "Q27") (pin "3") (pinfunction "C_3") (pintype "passive"))
      (node (ref "R49") (pin "2") (pinfunction "2_2") (pintype "passive"))
    )
    (net (code "21") (name "I_E_F2") (class "Default")
      (node (ref "Q28") (pin "3") (pinfunction "C_3") (pintype "passive"))
      (node (ref "R50") (pin "2") (pinfunction "2_2") (pintype "passive"))
    )
    (net (code "22") (name "I_E_F3") (class "Default")
      (node (ref "Q29") (pin "3") (pinfunction "C_3") (pintype "passive"))
      (node (ref "R51") (pin "2") (pinfunction "2_2") (pintype "passive"))
    )
    (net (code "23") (name "I_E_F4") (class "Default")
      (node (ref "Q30") (pin "3") (pinfunction "C_3") (pintype "passive"))
      (node (ref "R44") (pin "2") (pinfunction "2_2") (pintype "passive"))
    )
    (net (code "24") (name "Net-(C13-Pad2)") (class "Default")
      (node (ref "C13") (pin "2") (pinfunction "2_2") (pintype "passive"))
      (node (ref "R70") (pin "2") (pinfunction "2_2") (pintype "passive"))
    )
    (net (code "25") (name "Net-(C14-Pad2)") (class "Default")
      (node (ref "C14") (pin "2") (pinfunction "2_2") (pintype "passive"))
      (node (ref "R31") (pin "2") (pinfunction "2_2") (pintype "passive"))
      (node (ref "R32") (pin "2") (pinfunction "2_2") (pintype "passive"))
      (node (ref "R33") (pin "1") (pinfunction "1_1") (pintype "passive"))
    )
    (net (code "26") (name "Net-(D1-PadA)") (class "Default")
      (node (ref "D1") (pin "A") (pinfunction "A_A") (pintype "passive"))
      (node (ref "SV1") (pin "10") (pinfunction "10_10") (pintype "passive"))
      (node (ref "SV1") (pin "9") (pinfunction "9_9") (pintype "passive"))
    )
    (net (code "27") (name "Net-(D2-PadC)") (class "Default")
      (node (ref "D2") (pin "C") (pinfunction "C_C") (pintype "passive"))
      (node (ref "SV1") (pin "1") (pinfunction "1_1") (pintype "passive"))
      (node (ref "SV1") (pin "2") (pinfunction "2_2") (pintype "passive"))
    )
    (net (code "28") (name "Net-(IC1B--IN)") (class "Default")
      (node (ref "IC1") (pin "6") (pinfunction "-IN_6") (pintype "input"))
      (node (ref "IC1") (pin "7") (pinfunction "OUT_7") (pintype "output"))
      (node (ref "RV5") (pin "3") (pinfunction "E_3") (pintype "passive"))
    )
    (net (code "29") (name "Net-(IC1C--IN)") (class "Default")
      (node (ref "IC1") (pin "9") (pinfunction "-IN_9") (pintype "input"))
      (node (ref "R30") (pin "2") (pinfunction "2_2") (pintype "passive"))
      (node (ref "R31") (pin "1") (pinfunction "1_1") (pintype "passive"))
    )
    (net (code "30") (name "Net-(IC1C-OUT)") (class "Default")
      (node (ref "IC1") (pin "8") (pinfunction "OUT_8") (pintype "output"))
      (node (ref "R30") (pin "1") (pinfunction "1_1") (pintype "passive"))
      (node (ref "R43") (pin "2") (pinfunction "2_2") (pintype "passive"))
    )
    (net (code "31") (name "Net-(IC1D--IN)") (class "Default")
      (node (ref "IC1") (pin "13") (pinfunction "-IN_13") (pintype "input"))
      (node (ref "R27") (pin "1") (pinfunction "1_1") (pintype "passive"))
      (node (ref "R3") (pin "2") (pinfunction "2_2") (pintype "passive"))
      (node (ref "RV7") (pin "3") (pinfunction "E_3") (pintype "passive"))
    )
    (net (code "32") (name "Net-(IC2A--IN)") (class "Default")
      (node (ref "C17") (pin "1") (pinfunction "1_1") (pintype "passive"))
      (node (ref "IC2") (pin "2") (pinfunction "-IN_2") (pintype "input"))
      (node (ref "Q25") (pin "3") (pinfunction "C_3") (pintype "passive"))
      (node (ref "R69") (pin "2") (pinfunction "2_2") (pintype "passive"))
    )
    (net (code "33") (name "Net-(IC2A-OUT)") (class "Default")
      (node (ref "C17") (pin "2") (pinfunction "2_2") (pintype "passive"))
      (node (ref "IC2") (pin "1") (pinfunction "OUT_1") (pintype "output"))
      (node (ref "R48") (pin "2") (pinfunction "2_2") (pintype "passive"))
    )
    (net (code "34") (name "Net-(IC2B--IN)") (class "Default")
      (node (ref "IC2") (pin "6") (pinfunction "-IN_6") (pintype "input"))
      (node (ref "R1") (pin "1") (pinfunction "1_1") (pintype "passive"))
      (node (ref "R14") (pin "2") (pinfunction "2_2") (pintype "passive"))
      (node (ref "R7") (pin "1") (pinfunction "1_1") (pintype "passive"))
    )
    (net (code "35") (name "Net-(IC2B-OUT)") (class "Default")
      (node (ref "IC2") (pin "7") (pinfunction "OUT_7") (pintype "output"))
      (node (ref "R14") (pin "1") (pinfunction "1_1") (pintype "passive"))
      (node (ref "R26") (pin "2") (pinfunction "2_2") (pintype "passive"))
    )
    (net (code "36") (name "Net-(IC2C--IN)") (class "Default")
      (node (ref "IC2") (pin "9") (pinfunction "-IN_9") (pintype "input"))
      (node (ref "R13") (pin "2") (pinfunction "2_2") (pintype "passive"))
      (node (ref "R8") (pin "1") (pinfunction "1_1") (pintype "passive"))
      (node (ref "R9") (pin "1") (pinfunction "1_1") (pintype "passive"))
    )
    (net (code "37") (name "Net-(IC2C-OUT)") (class "Default")
      (node (ref "IC2") (pin "8") (pinfunction "OUT_8") (pintype "output"))
      (node (ref "R13") (pin "1") (pinfunction "1_1") (pintype "passive"))
      (node (ref "R35") (pin "2") (pinfunction "2_2") (pintype "passive"))
    )
    (net (code "38") (name "Net-(IC2D--IN)") (class "Default")
      (node (ref "C18") (pin "1") (pinfunction "1_1") (pintype "passive"))
      (node (ref "IC2") (pin "13") (pinfunction "-IN_13") (pintype "input"))
      (node (ref "Q26") (pin "3") (pinfunction "C_3") (pintype "passive"))
      (node (ref "R68") (pin "2") (pinfunction "2_2") (pintype "passive"))
    )
    (net (code "39") (name "Net-(IC2D-OUT)") (class "Default")
      (node (ref "C18") (pin "2") (pinfunction "2_2") (pintype "passive"))
      (node (ref "IC2") (pin "14") (pinfunction "OUT_14") (pintype "output"))
      (node (ref "R46") (pin "2") (pinfunction "2_2") (pintype "passive"))
    )
    (net (code "40") (name "Net-(IC3A--IN)") (class "Default")
      (node (ref "IC3") (pin "2") (pinfunction "-IN_2") (pintype "input"))
      (node (ref "R37") (pin "2") (pinfunction "2_2") (pintype "passive"))
      (node (ref "R38") (pin "1") (pinfunction "1_1") (pintype "passive"))
    )
    (net (code "41") (name "Net-(IC3A-OUT)") (class "Default")
      (node (ref "IC3") (pin "1") (pinfunction "OUT_1") (pintype "output"))
      (node (ref "R11") (pin "2") (pinfunction "2_2") (pintype "passive"))
      (node (ref "R37") (pin "1") (pinfunction "1_1") (pintype "passive"))
    )
    (net (code "42") (name "Net-(IC3B--IN)") (class "Default")
      (node (ref "IC3") (pin "6") (pinfunction "-IN_6") (pintype "input"))
      (node (ref "R4") (pin "2") (pinfunction "2_2") (pintype "passive"))
      (node (ref "R5") (pin "1") (pinfunction "1_1") (pintype "passive"))
      (node (ref "R6") (pin "1") (pinfunction "1_1") (pintype "passive"))
    )
    (net (code "43") (name "Net-(IC3C--IN)") (class "Default")
      (node (ref "IC3") (pin "8") (pinfunction "OUT_8") (pintype "output"))
      (node (ref "IC3") (pin "9") (pinfunction "-IN_9") (pintype "input"))
    )
    (net (code "44") (name "Net-(IC3D--IN)") (class "Default")
      (node (ref "IC3") (pin "13") (pinfunction "-IN_13") (pintype "input"))
      (node (ref "R10") (pin "2") (pinfunction "2_2") (pintype "passive"))
      (node (ref "R11") (pin "1") (pinfunction "1_1") (pintype "passive"))
      (node (ref "R12") (pin "1") (pinfunction "1_1") (pintype "passive"))
    )
    (net (code "45") (name "Net-(IC3D-OUT)") (class "Default")
      (node (ref "IC3") (pin "14") (pinfunction "OUT_14") (pintype "output"))
      (node (ref "R10") (pin "1") (pinfunction "1_1") (pintype "passive"))
      (node (ref "R67") (pin "2") (pinfunction "2_2") (pintype "passive"))
    )
    (net (code "46") (name "Net-(Q1A-B)") (class "Default")
      (node (ref "Q1") (pin "1") (pinfunction "B_1") (pintype "passive"))
      (node (ref "R16") (pin "1") (pinfunction "1_1") (pintype "passive"))
      (node (ref "R17") (pin "2") (pinfunction "2_2") (pintype "passive"))
      (node (ref "R57") (pin "1") (pinfunction "1_1") (pintype "passive"))
    )
    (net (code "47") (name "Net-(Q1A-E)") (class "Default")
      (node (ref "Q1") (pin "4") (pinfunction "E_4") (pintype "passive"))
      (node (ref "Q1") (pin "5") (pinfunction "E_5") (pintype "passive"))
      (node (ref "R49") (pin "1") (pinfunction "1_1") (pintype "passive"))
    )
    (net (code "48") (name "Net-(Q1B-B)") (class "Default")
      (node (ref "Q1") (pin "2") (pinfunction "B_2") (pintype "passive"))
      (node (ref "R56") (pin "1") (pinfunction "1_1") (pintype "passive"))
    )
    (net (code "49") (name "Net-(Q1B-C)") (class "Default")
      (node (ref "Q1") (pin "3") (pinfunction "C_3") (pintype "passive"))
      (node (ref "Q7") (pin "1") (pinfunction "B_1") (pintype "passive"))
      (node (ref "Q7") (pin "2") (pinfunction "B_2") (pintype "passive"))
      (node (ref "Q7") (pin "6") (pinfunction "C_6") (pintype "passive"))
    )
    (net (code "50") (name "Net-(Q2A-B)") (class "Default")
      (node (ref "Q2") (pin "1") (pinfunction "B_1") (pintype "passive"))
      (node (ref "R19") (pin "1") (pinfunction "1_1") (pintype "passive"))
      (node (ref "R21") (pin "2") (pinfunction "2_2") (pintype "passive"))
      (node (ref "R59") (pin "1") (pinfunction "1_1") (pintype "passive"))
    )
    (net (code "51") (name "Net-(Q2A-E)") (class "Default")
      (node (ref "Q2") (pin "4") (pinfunction "E_4") (pintype "passive"))
      (node (ref "Q2") (pin "5") (pinfunction "E_5") (pintype "passive"))
      (node (ref "R50") (pin "1") (pinfunction "1_1") (pintype "passive"))
    )
    (net (code "52") (name "Net-(Q2B-B)") (class "Default")
      (node (ref "Q2") (pin "2") (pinfunction "B_2") (pintype "passive"))
      (node (ref "R58") (pin "1") (pinfunction "1_1") (pintype "passive"))
    )
    (net (code "53") (name "Net-(Q2B-C)") (class "Default")
      (node (ref "Q2") (pin "3") (pinfunction "C_3") (pintype "passive"))
      (node (ref "Q8") (pin "1") (pinfunction "B_1") (pintype "passive"))
      (node (ref "Q8") (pin "2") (pinfunction "B_2") (pintype "passive"))
      (node (ref "Q8") (pin "6") (pinfunction "C_6") (pintype "passive"))
    )
    (net (code "54") (name "Net-(Q3A-B)") (class "Default")
      (node (ref "Q3") (pin "1") (pinfunction "B_1") (pintype "passive"))
      (node (ref "R63") (pin "1") (pinfunction "1_1") (pintype "passive"))
    )
    (net (code "55") (name "Net-(Q3A-E)") (class "Default")
      (node (ref "Q3") (pin "4") (pinfunction "E_4") (pintype "passive"))
      (node (ref "Q3") (pin "5") (pinfunction "E_5") (pintype "passive"))
      (node (ref "R26") (pin "1") (pinfunction "1_1") (pintype "passive"))
    )
    (net (code "56") (name "Net-(Q3B-B)") (class "Default")
      (node (ref "Q3") (pin "2") (pinfunction "B_2") (pintype "passive"))
      (node (ref "R40") (pin "1") (pinfunction "1_1") (pintype "passive"))
      (node (ref "R62") (pin "1") (pinfunction "1_1") (pintype "passive"))
    )
    (net (code "57") (name "Net-(Q3B-C)") (class "Default")
      (node (ref "Q3") (pin "3") (pinfunction "C_3") (pintype "passive"))
      (node (ref "Q9") (pin "1") (pinfunction "B_1") (pintype "passive"))
      (node (ref "Q9") (pin "2") (pinfunction "B_2") (pintype "passive"))
      (node (ref "Q9") (pin "6") (pinfunction "C_6") (pintype "passive"))
    )
    (net (code "58") (name "Net-(Q4A-B)") (class "Default")
      (node (ref "Q4") (pin "1") (pinfunction "B_1") (pintype "passive"))
      (node (ref "R22") (pin "1") (pinfunction "1_1") (pintype "passive"))
      (node (ref "R24") (pin "2") (pinfunction "2_2") (pintype "passive"))
      (node (ref "R61") (pin "1") (pinfunction "1_1") (pintype "passive"))
    )
    (net (code "59") (name "Net-(Q4A-E)") (class "Default")
      (node (ref "Q4") (pin "4") (pinfunction "E_4") (pintype "passive"))
      (node (ref "Q4") (pin "5") (pinfunction "E_5") (pintype "passive"))
      (node (ref "R51") (pin "1") (pinfunction "1_1") (pintype "passive"))
    )
    (net (code "60") (name "Net-(Q4B-B)") (class "Default")
      (node (ref "Q4") (pin "2") (pinfunction "B_2") (pintype "passive"))
      (node (ref "R60") (pin "1") (pinfunction "1_1") (pintype "passive"))
    )
    (net (code "61") (name "Net-(Q5A-B)") (class "Default")
      (node (ref "Q5") (pin "1") (pinfunction "B_1") (pintype "passive"))
      (node (ref "R29") (pin "2") (pinfunction "2_2") (pintype "passive"))
      (node (ref "R39") (pin "1") (pinfunction "1_1") (pintype "passive"))
      (node (ref "R53") (pin "1") (pinfunction "1_1") (pintype "passive"))
    )
    (net (code "62") (name "Net-(Q5A-E)") (class "Default")
      (node (ref "Q5") (pin "4") (pinfunction "E_4") (pintype "passive"))
      (node (ref "Q5") (pin "5") (pinfunction "E_5") (pintype "passive"))
      (node (ref "R44") (pin "1") (pinfunction "1_1") (pintype "passive"))
    )
    (net (code "63") (name "Net-(Q5B-B)") (class "Default")
      (node (ref "Q5") (pin "2") (pinfunction "B_2") (pintype "passive"))
      (node (ref "R52") (pin "1") (pinfunction "1_1") (pintype "passive"))
    )
    (net (code "64") (name "Net-(Q6A-B)") (class "Default")
      (node (ref "Q6") (pin "1") (pinfunction "B_1") (pintype "passive"))
      (node (ref "R55") (pin "1") (pinfunction "1_1") (pintype "passive"))
    )
    (net (code "65") (name "Net-(Q6A-E)") (class "Default")
      (node (ref "Q6") (pin "4") (pinfunction "E_4") (pintype "passive"))
      (node (ref "Q6") (pin "5") (pinfunction "E_5") (pintype "passive"))
      (node (ref "R35") (pin "1") (pinfunction "1_1") (pintype "passive"))
    )
    (net (code "66") (name "Net-(Q6B-B)") (class "Default")
      (node (ref "Q6") (pin "2") (pinfunction "B_2") (pintype "passive"))
      (node (ref "R34") (pin "1") (pinfunction "1_1") (pintype "passive"))
      (node (ref "R54") (pin "1") (pinfunction "1_1") (pintype "passive"))
    )
    (net (code "67") (name "Net-(Q10A-B)") (class "Default")
      (node (ref "Q10") (pin "1") (pinfunction "B_1") (pintype "passive"))
      (node (ref "Q10") (pin "2") (pinfunction "B_2") (pintype "passive"))
      (node (ref "Q10") (pin "6") (pinfunction "C_6") (pintype "passive"))
      (node (ref "Q4") (pin "3") (pinfunction "C_3") (pintype "passive"))
    )
    (net (code "68") (name "Net-(Q10B-C)") (class "Default")
      (node (ref "C11") (pin "1") (pinfunction "1_1") (pintype "passive"))
      (node (ref "Q10") (pin "3") (pinfunction "C_3") (pintype "passive"))
      (node (ref "Q19") (pin "1") (pinfunction "B_1") (pintype "passive"))
      (node (ref "Q4") (pin "6") (pinfunction "C_6") (pintype "passive"))
    )
    (net (code "69") (name "Net-(Q11A-B)") (class "Default")
      (node (ref "Q11") (pin "1") (pinfunction "B_1") (pintype "passive"))
      (node (ref "Q11") (pin "2") (pinfunction "B_2") (pintype "passive"))
      (node (ref "Q11") (pin "6") (pinfunction "C_6") (pintype "passive"))
      (node (ref "Q5") (pin "3") (pinfunction "C_3") (pintype "passive"))
    )
    (net (code "70") (name "Net-(Q11B-C)") (class "Default")
      (node (ref "C12") (pin "1") (pinfunction "1_1") (pintype "passive"))
      (node (ref "Q11") (pin "3") (pinfunction "C_3") (pintype "passive"))
      (node (ref "Q21") (pin "1") (pinfunction "B_1") (pintype "passive"))
      (node (ref "Q5") (pin "6") (pinfunction "C_6") (pintype "passive"))
    )
    (net (code "71") (name "Net-(Q12A-B)") (class "Default")
      (node (ref "Q12") (pin "1") (pinfunction "B_1") (pintype "passive"))
      (node (ref "Q12") (pin "2") (pinfunction "B_2") (pintype "passive"))
      (node (ref "Q12") (pin "6") (pinfunction "C_6") (pintype "passive"))
      (node (ref "Q6") (pin "3") (pinfunction "C_3") (pintype "passive"))
    )
    (net (code "72") (name "Net-(Q12B-C)") (class "Default")
      (node (ref "Q12") (pin "3") (pinfunction "C_3") (pintype "passive"))
      (node (ref "Q23") (pin "1") (pinfunction "B_1") (pintype "passive"))
      (node (ref "Q6") (pin "6") (pinfunction "C_6") (pintype "passive"))
      (node (ref "R45") (pin "1") (pinfunction "1_1") (pintype "passive"))
    )
    (net (code "73") (name "Net-(Q13-B)") (class "Default")
      (node (ref "C9") (pin "1") (pinfunction "1_1") (pintype "passive"))
      (node (ref "Q1") (pin "6") (pinfunction "C_6") (pintype "passive"))
      (node (ref "Q13") (pin "1") (pinfunction "B_1") (pintype "passive"))
      (node (ref "Q7") (pin "3") (pinfunction "C_3") (pintype "passive"))
    )
    (net (code "74") (name "Net-(Q13-E)") (class "Default")
      (node (ref "Q13") (pin "2") (pinfunction "E_2") (pintype "passive"))
      (node (ref "Q14") (pin "1") (pinfunction "B_1") (pintype "passive"))
    )
    (net (code "75") (name "Net-(Q15-B)") (class "Default")
      (node (ref "C10") (pin "1") (pinfunction "1_1") (pintype "passive"))
      (node (ref "Q15") (pin "1") (pinfunction "B_1") (pintype "passive"))
      (node (ref "Q2") (pin "6") (pinfunction "C_6") (pintype "passive"))
      (node (ref "Q8") (pin "3") (pinfunction "C_3") (pintype "passive"))
    )
    (net (code "76") (name "Net-(Q15-E)") (class "Default")
      (node (ref "Q15") (pin "2") (pinfunction "E_2") (pintype "passive"))
      (node (ref "Q16") (pin "1") (pinfunction "B_1") (pintype "passive"))
    )
    (net (code "77") (name "Net-(Q17-B)") (class "Default")
      (node (ref "Q17") (pin "1") (pinfunction "B_1") (pintype "passive"))
      (node (ref "Q3") (pin "6") (pinfunction "C_6") (pintype "passive"))
      (node (ref "Q9") (pin "3") (pinfunction "C_3") (pintype "passive"))
      (node (ref "R47") (pin "1") (pinfunction "1_1") (pintype "passive"))
    )
    (net (code "78") (name "Net-(Q17-E)") (class "Default")
      (node (ref "Q17") (pin "2") (pinfunction "E_2") (pintype "passive"))
      (node (ref "Q18") (pin "1") (pinfunction "B_1") (pintype "passive"))
    )
    (net (code "79") (name "Net-(Q18-E)") (class "Default")
      (node (ref "C13") (pin "1") (pinfunction "1_1") (pintype "passive"))
      (node (ref "Q18") (pin "2") (pinfunction "E_2") (pintype "passive"))
      (node (ref "R15") (pin "1") (pinfunction "1_1") (pintype "passive"))
    )
    (net (code "80") (name "Net-(Q19-E)") (class "Default")
      (node (ref "Q19") (pin "2") (pinfunction "E_2") (pintype "passive"))
      (node (ref "Q20") (pin "1") (pinfunction "B_1") (pintype "passive"))
    )
    (net (code "81") (name "Net-(Q21-E)") (class "Default")
      (node (ref "Q21") (pin "2") (pinfunction "E_2") (pintype "passive"))
      (node (ref "Q22") (pin "1") (pinfunction "B_1") (pintype "passive"))
    )
    (net (code "82") (name "Net-(Q23-E)") (class "Default")
      (node (ref "Q23") (pin "2") (pinfunction "E_2") (pintype "passive"))
      (node (ref "Q24") (pin "1") (pinfunction "B_1") (pintype "passive"))
    )
    (net (code "83") (name "Net-(Q25-E)") (class "Default")
      (node (ref "Q25") (pin "2") (pinfunction "E_2") (pintype "passive"))
      (node (ref "Q27") (pin "2") (pinfunction "E_2") (pintype "passive"))
      (node (ref "Q28") (pin "2") (pinfunction "E_2") (pintype "passive"))
      (node (ref "R48") (pin "1") (pinfunction "1_1") (pintype "passive"))
    )
    (net (code "84") (name "Net-(Q26-E)") (class "Default")
      (node (ref "Q26") (pin "2") (pinfunction "E_2") (pintype "passive"))
      (node (ref "Q29") (pin "2") (pinfunction "E_2") (pintype "passive"))
      (node (ref "Q30") (pin "2") (pinfunction "E_2") (pintype "passive"))
      (node (ref "R46") (pin "1") (pinfunction "1_1") (pintype "passive"))
    )
    (net (code "85") (name "Net-(RV1-A)") (class "Default")
      (node (ref "R42") (pin "1") (pinfunction "1_1") (pintype "passive"))
      (node (ref "RV1") (pin "1") (pinfunction "A_1") (pintype "passive"))
    )
    (net (code "86") (name "Net-(RV1-E)") (class "Default")
      (node (ref "R41") (pin "2") (pinfunction "2_2") (pintype "passive"))
      (node (ref "RV1") (pin "3") (pinfunction "E_3") (pintype "passive"))
    )
    (net (code "87") (name "Net-(RV1-S)") (class "Default")
      (node (ref "R6") (pin "2") (pinfunction "2_2") (pintype "passive"))
      (node (ref "RV1") (pin "2") (pinfunction "S_2") (pintype "passive"))
    )
    (net (code "88") (name "Net-(RV2-S)") (class "Default")
      (node (ref "R5") (pin "2") (pinfunction "2_2") (pintype "passive"))
      (node (ref "RV2") (pin "2") (pinfunction "S_2") (pintype "passive"))
    )
    (net (code "89") (name "Net-(RV3-S)") (class "Default")
      (node (ref "R7") (pin "2") (pinfunction "2_2") (pintype "passive"))
      (node (ref "RV3") (pin "2") (pinfunction "S_2") (pintype "passive"))
    )
    (net (code "90") (name "Net-(RV4-S)") (class "Default")
      (node (ref "R9") (pin "2") (pinfunction "2_2") (pintype "passive"))
      (node (ref "RV4") (pin "2") (pinfunction "S_2") (pintype "passive"))
    )
    (net (code "91") (name "Net-(RV5-S)") (class "Default")
      (node (ref "R2") (pin "2") (pinfunction "2_2") (pintype "passive"))
      (node (ref "RV5") (pin "2") (pinfunction "S_2") (pintype "passive"))
    )
    (net (code "92") (name "Net-(RV6-S)") (class "Default")
      (node (ref "R70") (pin "1") (pinfunction "1_1") (pintype "passive"))
      (node (ref "RV6") (pin "2") (pinfunction "S_2") (pintype "passive"))
    )
    (net (code "93") (name "Net-(RV7-S)") (class "Default")
      (node (ref "R43") (pin "1") (pinfunction "1_1") (pintype "passive"))
      (node (ref "RV7") (pin "2") (pinfunction "S_2") (pintype "passive"))
    )
    (net (code "94") (name "OUT_1") (class "Default")
      (node (ref "C10") (pin "2") (pinfunction "2_2") (pintype "passive"))
      (node (ref "Q14") (pin "2") (pinfunction "E_2") (pintype "passive"))
      (node (ref "R17") (pin "1") (pinfunction "1_1") (pintype "passive"))
      (node (ref "R18") (pin "1") (pinfunction "1_1") (pintype "passive"))
      (node (ref "R19") (pin "2") (pinfunction "2_2") (pintype "passive"))
    )
    (net (code "95") (name "OUT_2") (class "Default")
      (node (ref "C11") (pin "2") (pinfunction "2_2") (pintype "passive"))
      (node (ref "Q16") (pin "2") (pinfunction "E_2") (pintype "passive"))
      (node (ref "R20") (pin "1") (pinfunction "1_1") (pintype "passive"))
      (node (ref "R21") (pin "1") (pinfunction "1_1") (pintype "passive"))
      (node (ref "R22") (pin "2") (pinfunction "2_2") (pintype "passive"))
      (node (ref "R40") (pin "2") (pinfunction "2_2") (pintype "passive"))
    )
    (net (code "96") (name "OUT_3") (class "Default")
      (node (ref "C12") (pin "2") (pinfunction "2_2") (pintype "passive"))
      (node (ref "Q20") (pin "2") (pinfunction "E_2") (pintype "passive"))
      (node (ref "R23") (pin "1") (pinfunction "1_1") (pintype "passive"))
      (node (ref "R24") (pin "1") (pinfunction "1_1") (pintype "passive"))
      (node (ref "R39") (pin "2") (pinfunction "2_2") (pintype "passive"))
    )
    (net (code "97") (name "unconnected-(IC4-REF-Pad1)") (class "Default")
      (node (ref "IC4") (pin "1") (pinfunction "REF_1") (pintype "no_connect"))
    )
    (net (code "98") (name "unconnected-(RV6-A-Pad1)") (class "Default")
      (node (ref "RV6") (pin "1") (pinfunction "A_1") (pintype "passive"))
    )
    (net (code "99") (name "unconnected-(RV7-A-Pad1)") (class "Default")
      (node (ref "RV7") (pin "1") (pinfunction "A_1") (pintype "passive"))
    )
    (net (code "100") (name "unconnected-(SV1-Pad11)") (class "Default")
      (node (ref "SV1") (pin "11") (pinfunction "11_11") (pintype "passive"))
    )
    (net (code "101") (name "unconnected-(SV1-Pad12)") (class "Default")
      (node (ref "SV1") (pin "12") (pinfunction "12_12") (pintype "passive"))
    )
    (net (code "102") (name "unconnected-(SV1-Pad13)") (class "Default")
      (node (ref "SV1") (pin "13") (pinfunction "13_13") (pintype "passive"))
    )
    (net (code "103") (name "unconnected-(SV1-Pad14)") (class "Default")
      (node (ref "SV1") (pin "14") (pinfunction "14_14") (pintype "passive"))
    )
    (net (code "104") (name "unconnected-(SV1-Pad15)") (class "Default")
      (node (ref "SV1") (pin "15") (pinfunction "15_15") (pintype "passive"))
    )
    (net (code "105") (name "unconnected-(SV1-Pad16)") (class "Default")
      (node (ref "SV1") (pin "16") (pinfunction "16_16") (pintype "passive"))
    )
  )
)
